# CrowBot_-V1_4-20220909.net
KiCad netlist of a schematic drawn in EAGLE
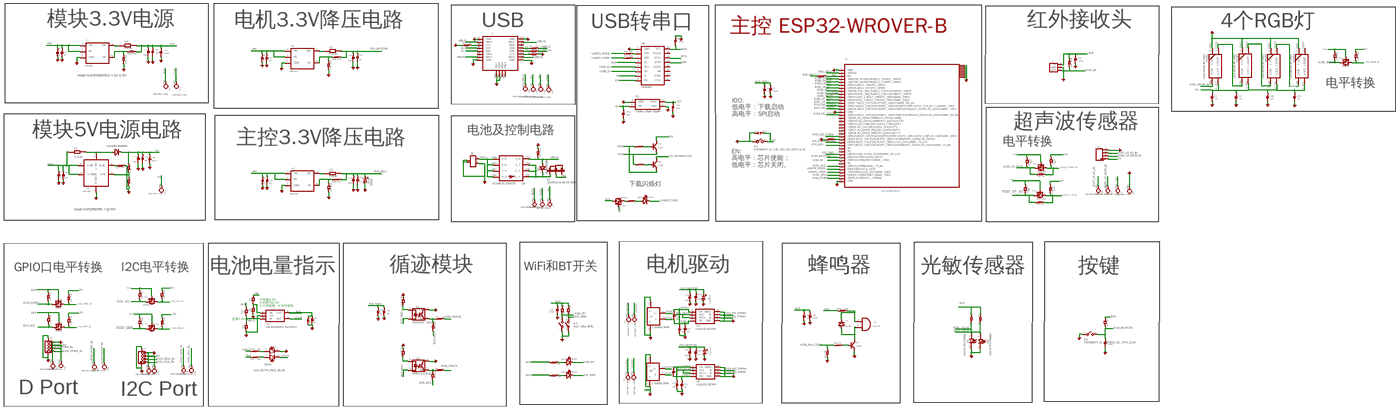
[diagram p0: schematic, sheet 1, overview]
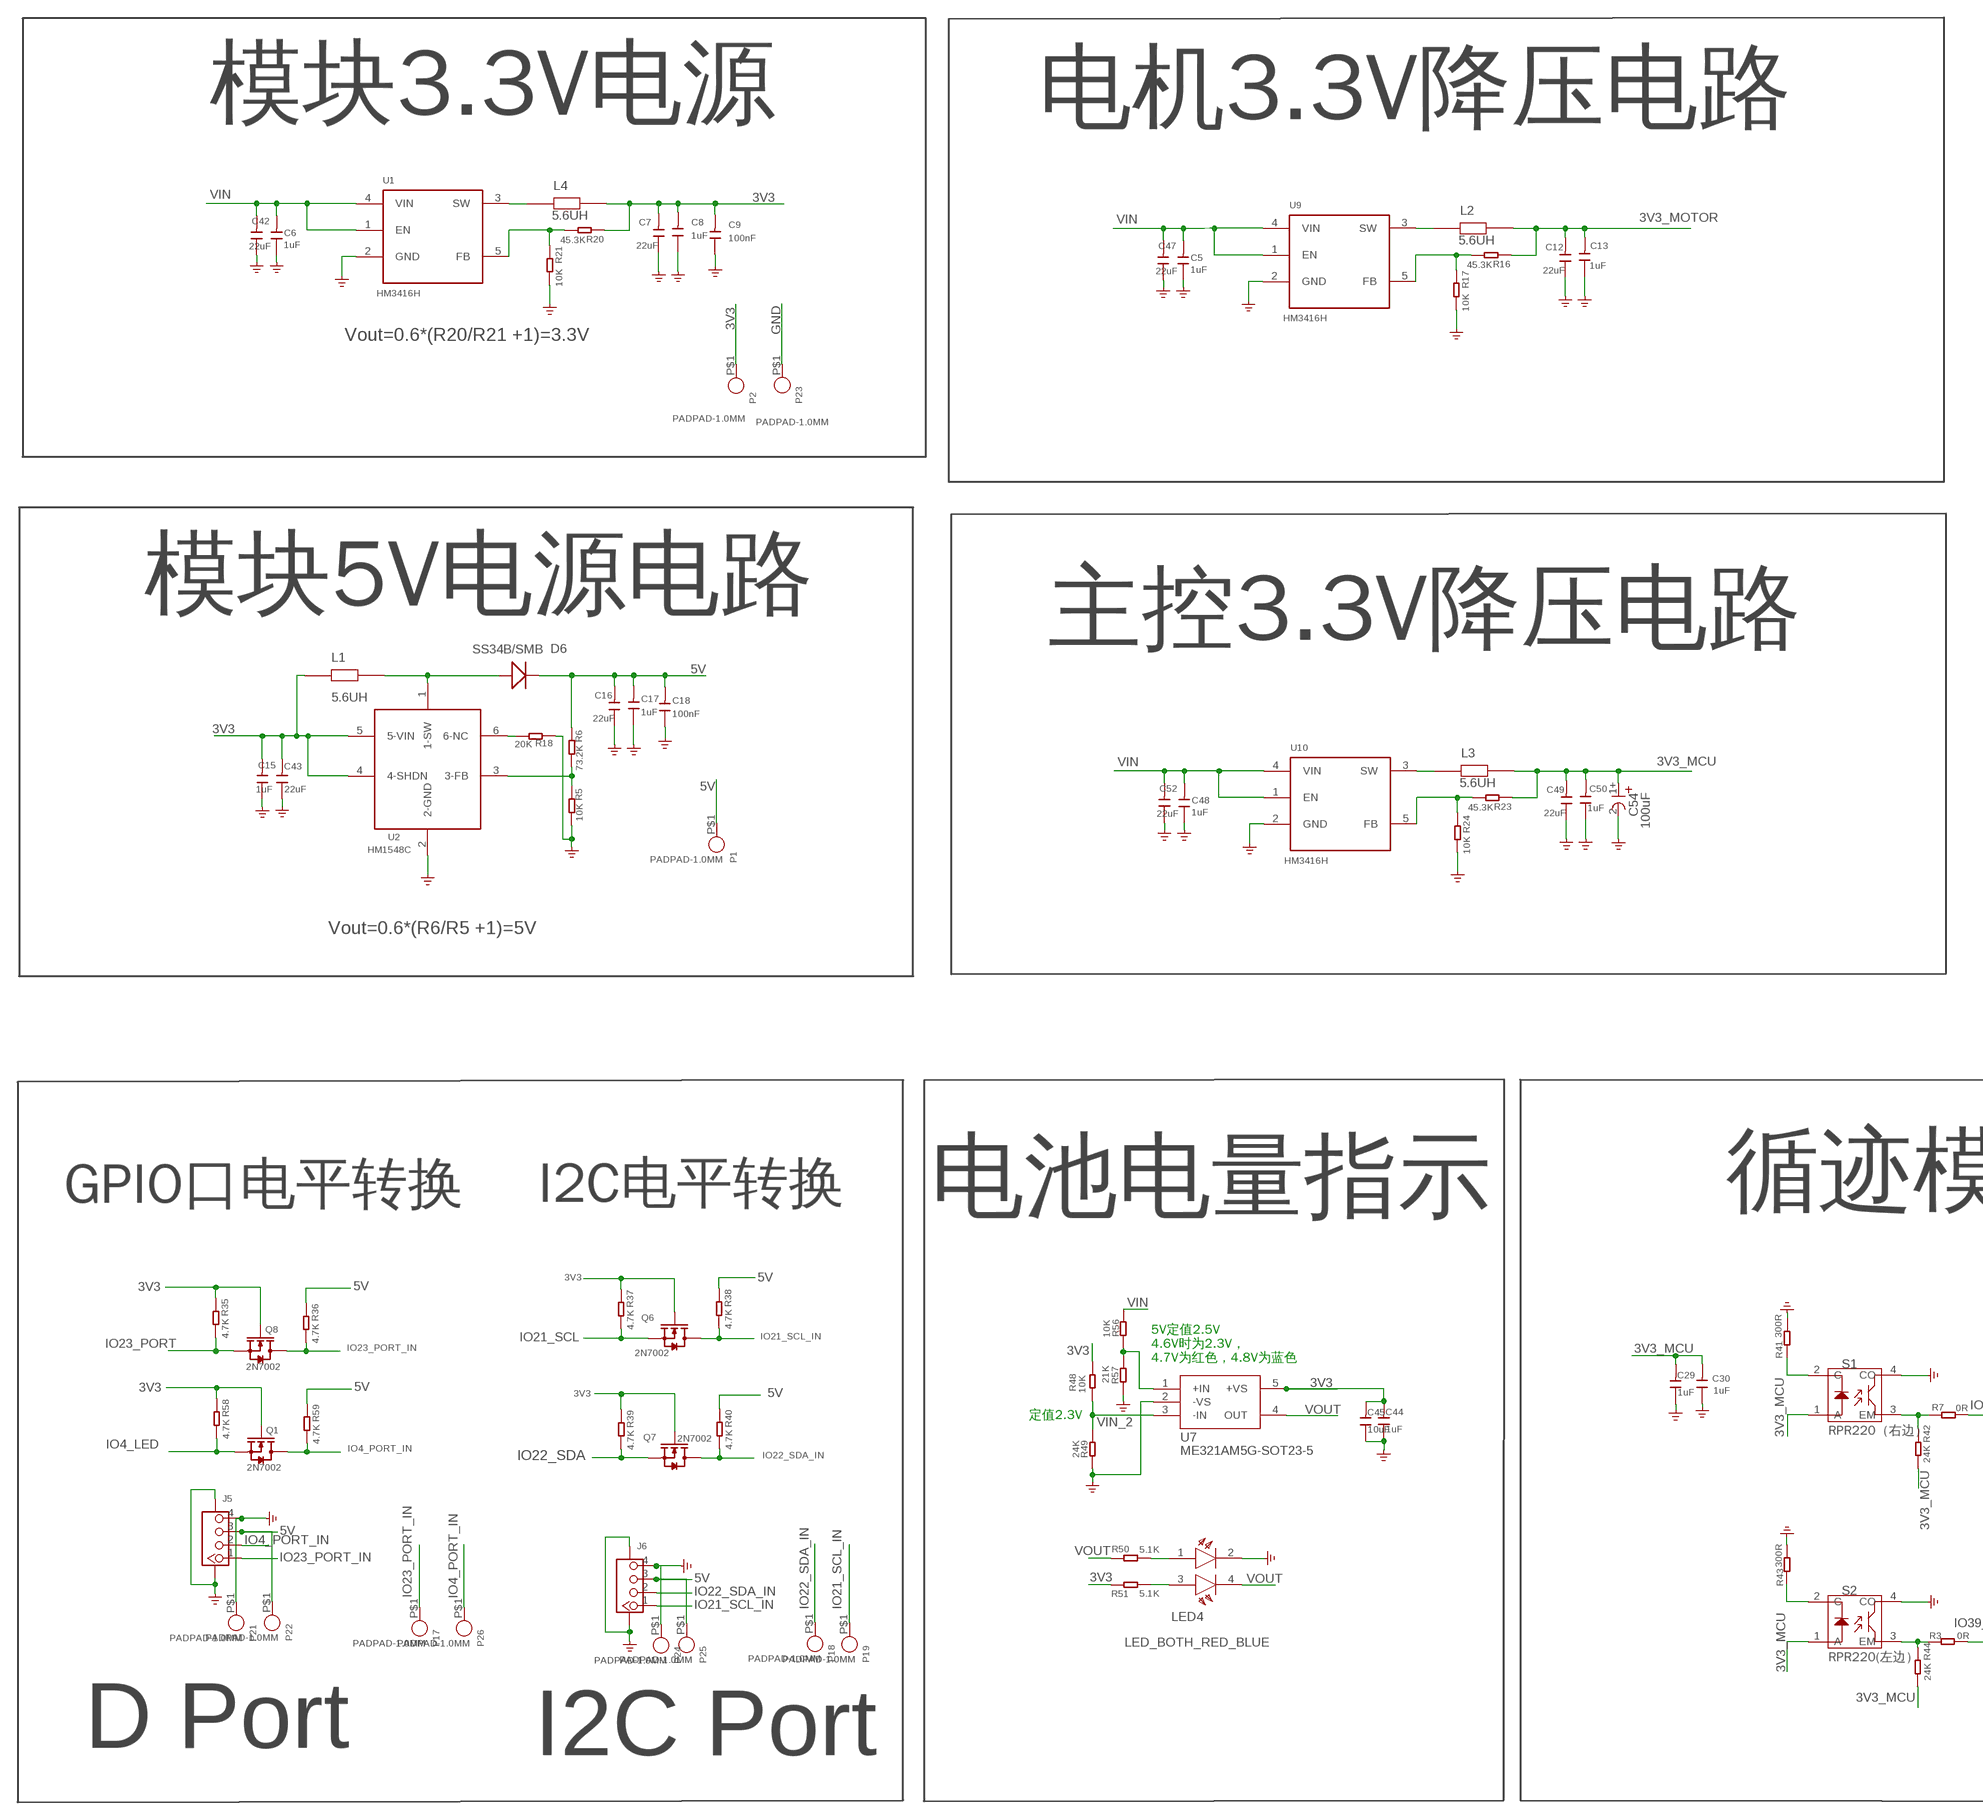
[diagram p1: schematic, sheet 1, part 1 of 4]
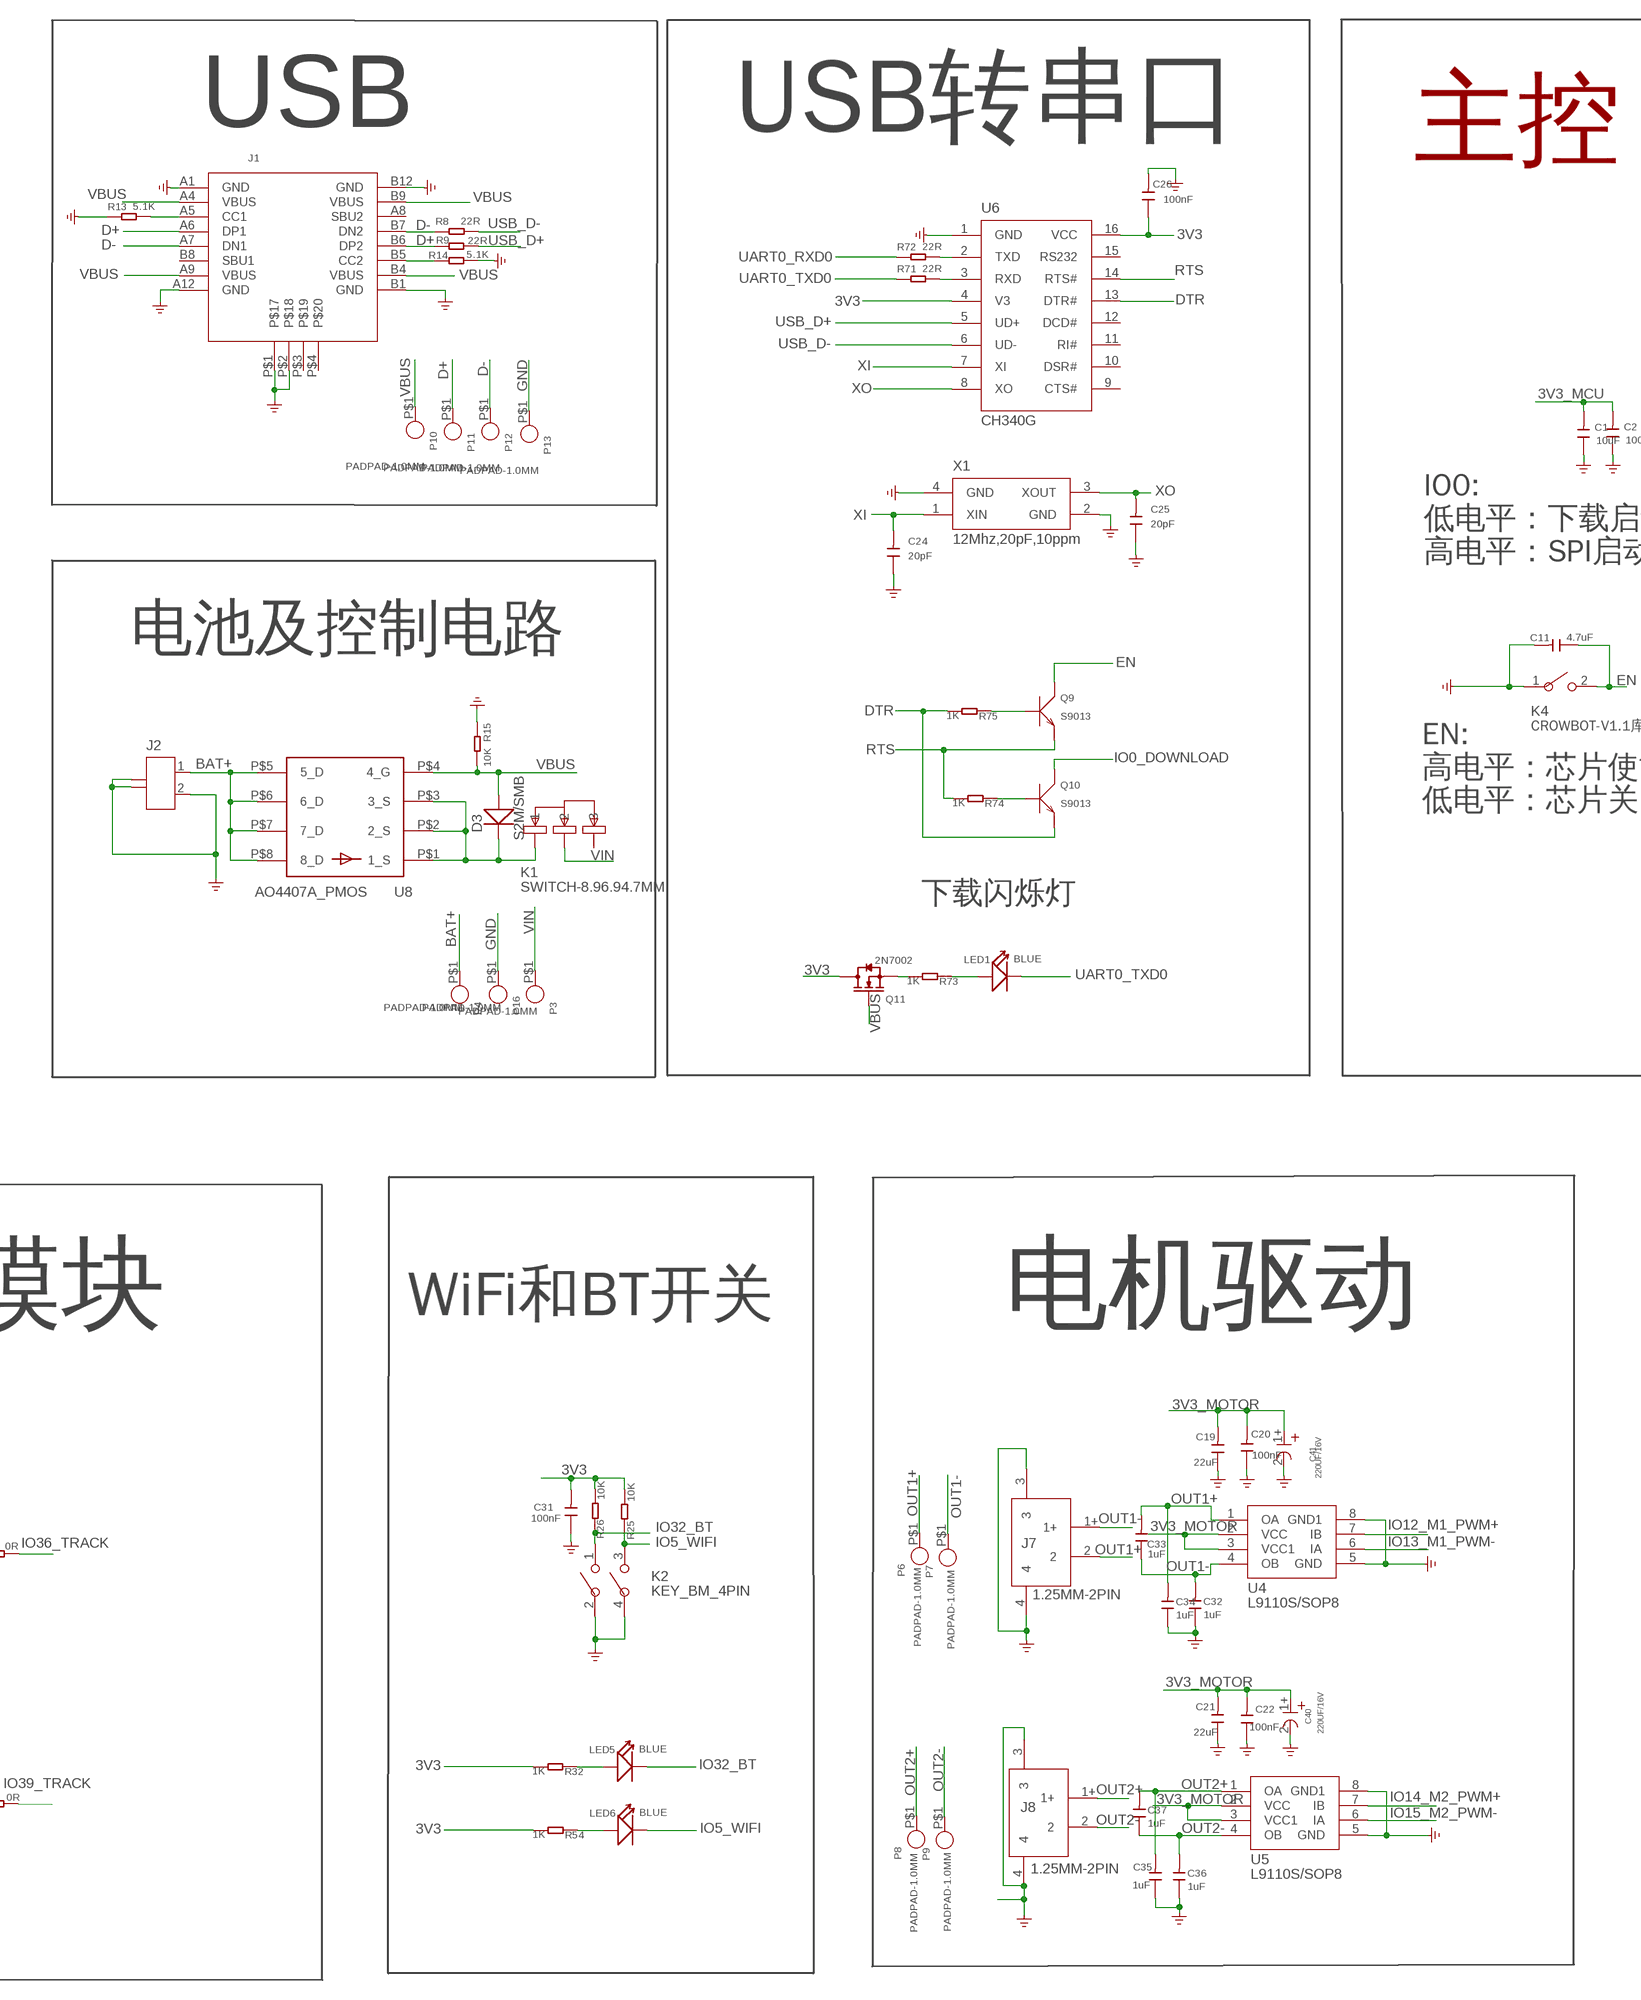
[diagram p2: schematic, sheet 1, part 2 of 4]
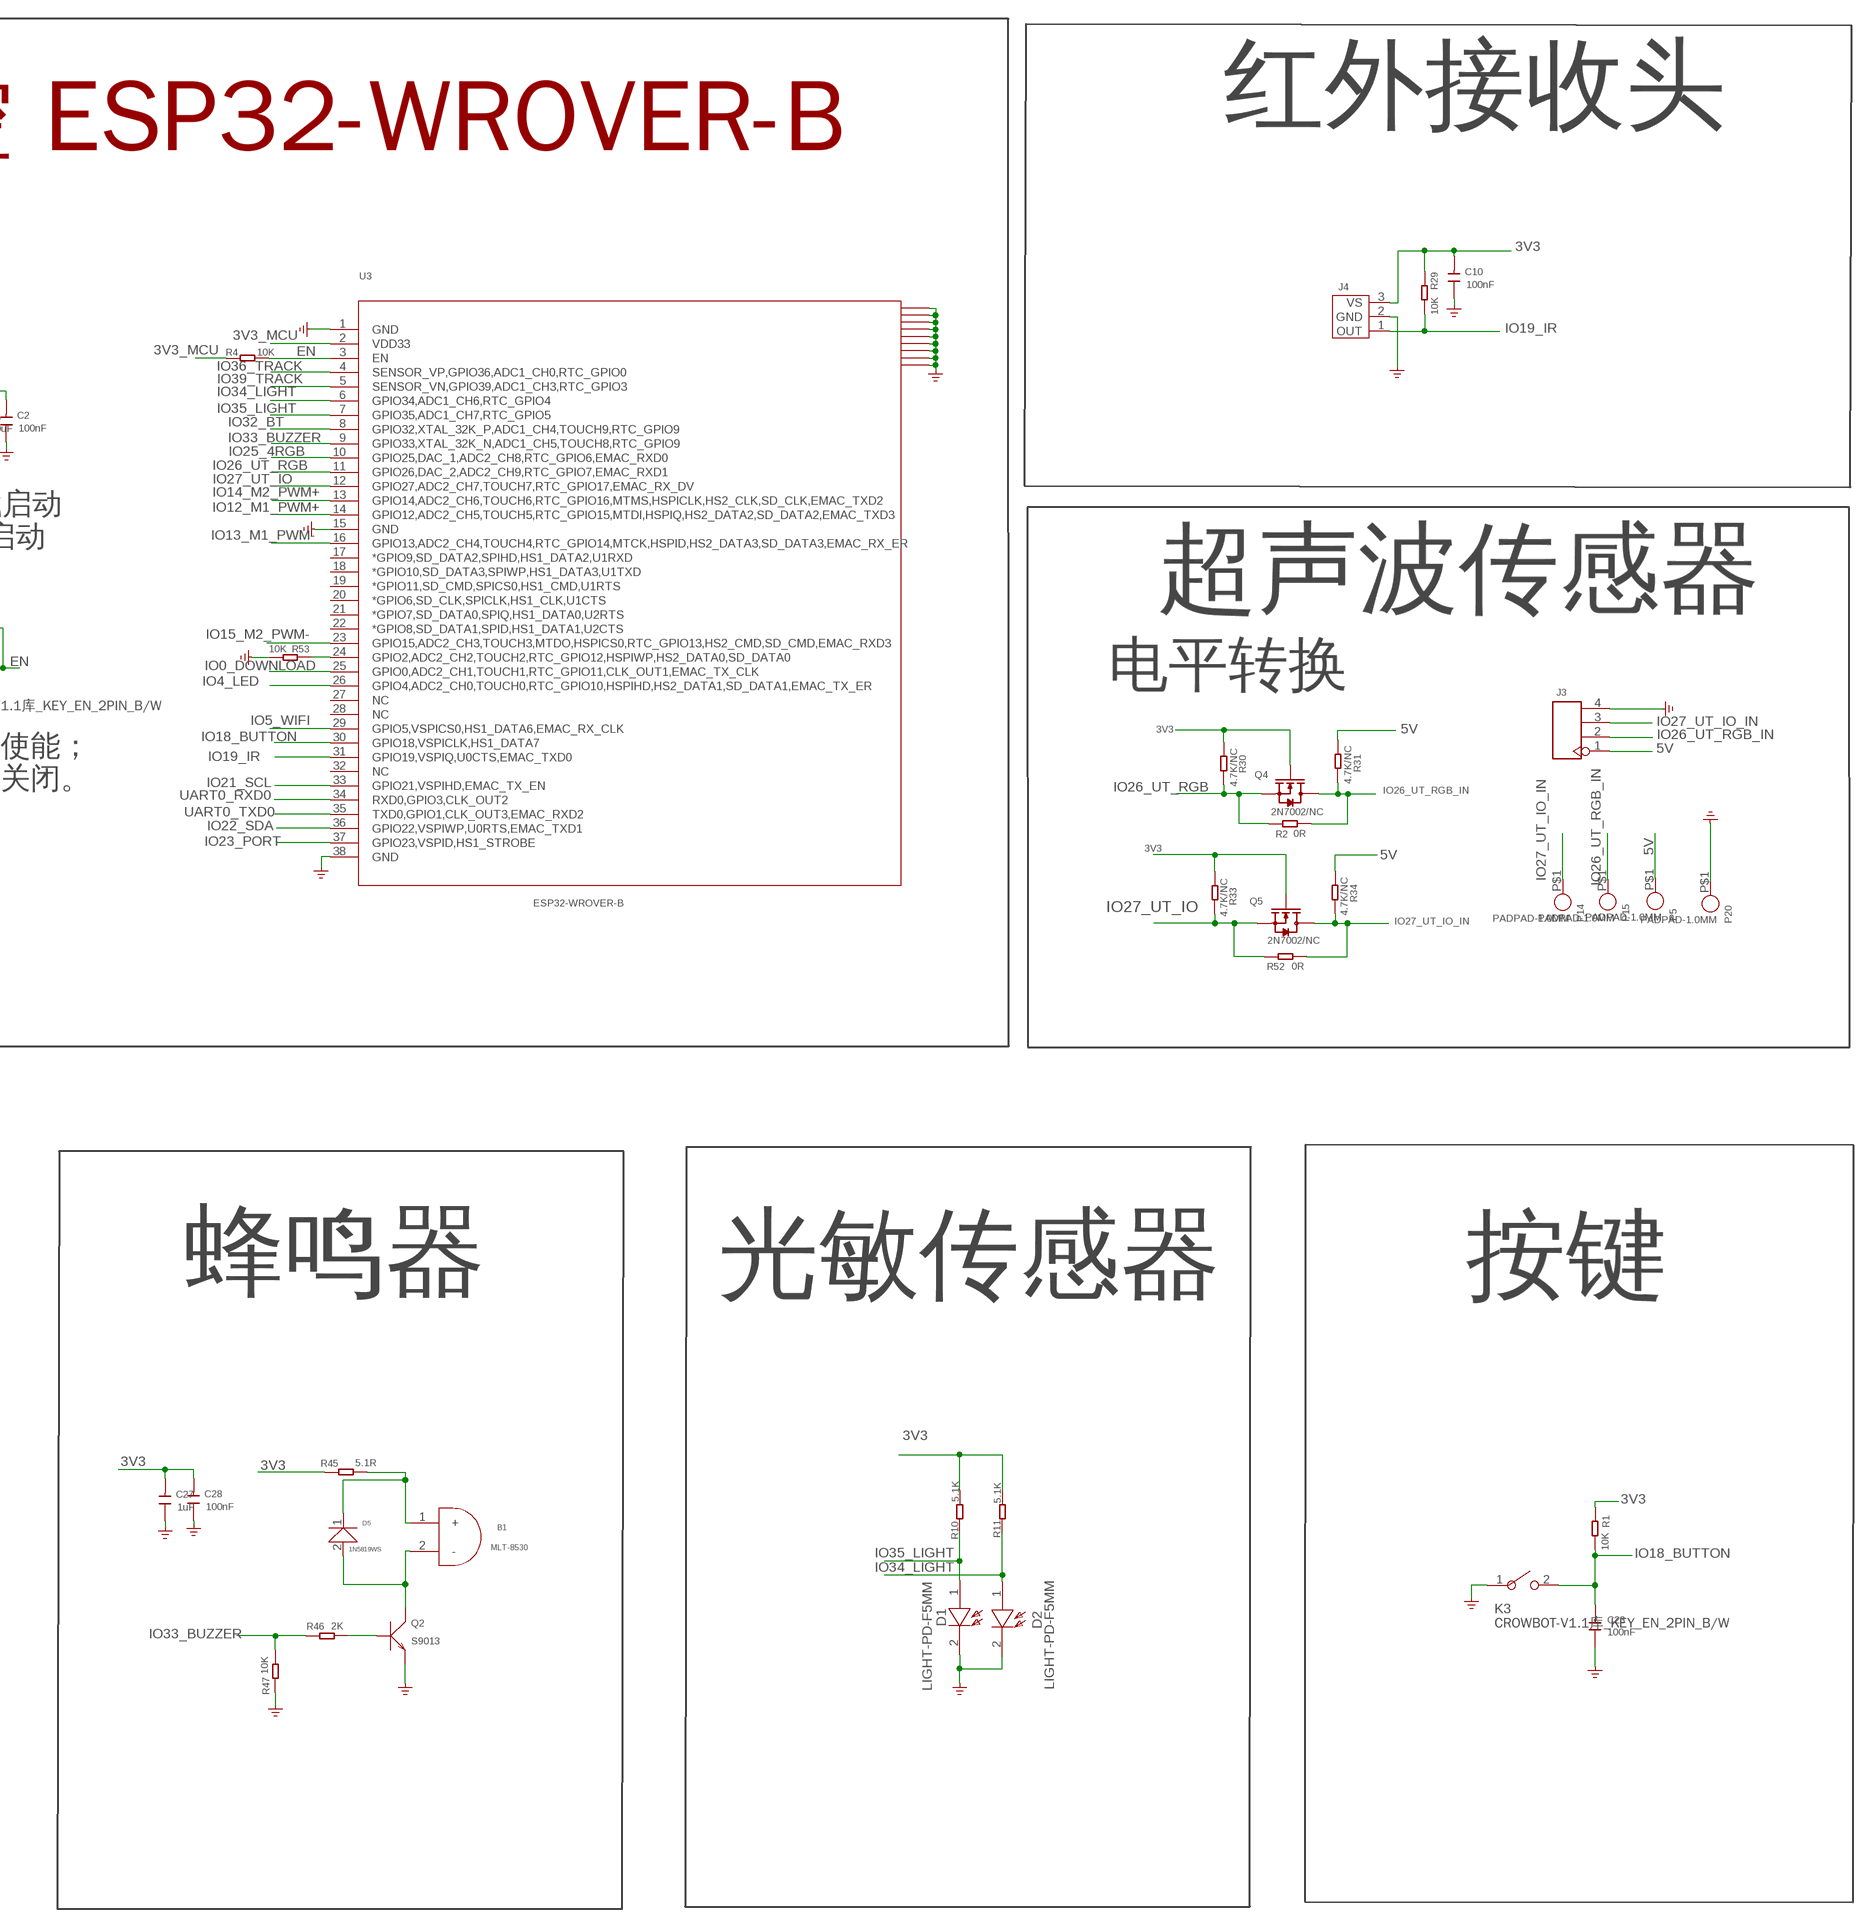
[diagram p3: schematic, sheet 1, part 3 of 4]
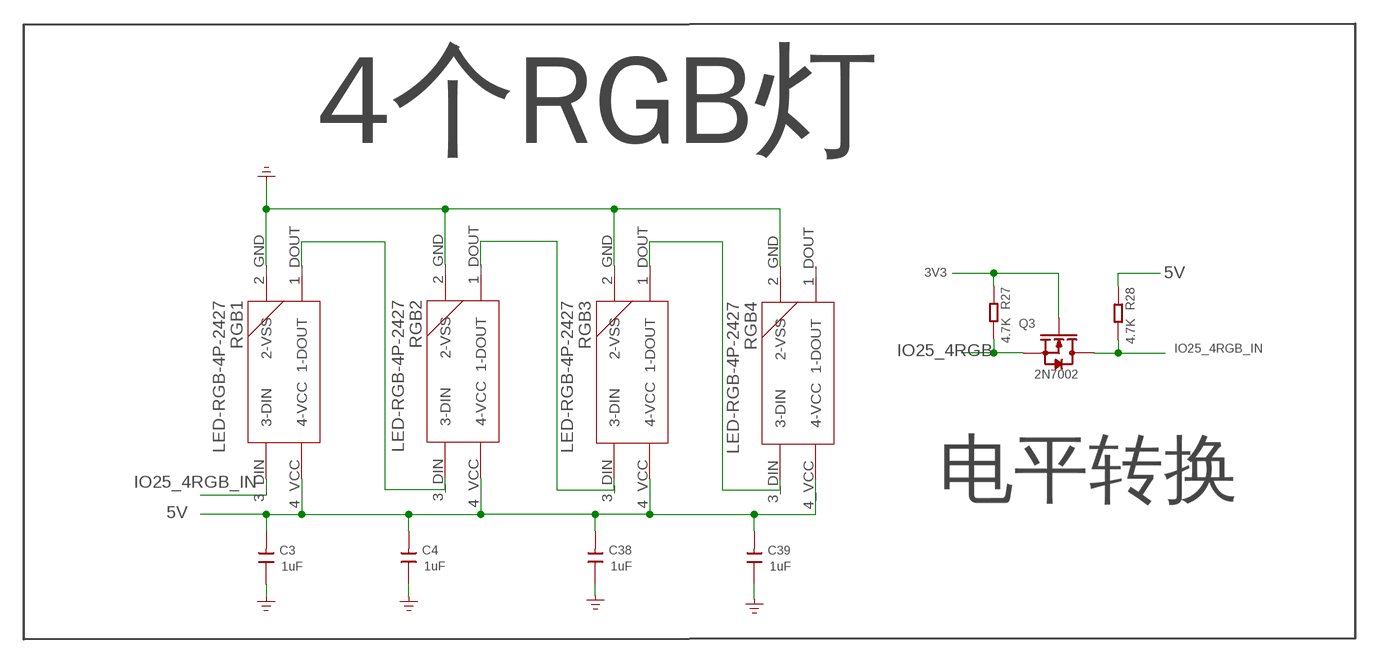
[diagram p4: schematic, sheet 1, part 4 of 4]

(export (version "E")
  (design (tool "Eeschema 10.0.6"))
  (components
    (comp (ref "B1")
      (value "MLT-8530")
      (footprint "eagle-import:MLT-8530")
      (libsource (lib "eagle-import") (part "MLT-8530"))
    )
    (comp (ref "C1")
      (value "10uF")
      (footprint "eagle-import:DISCRETE_C0603")
      (libsource (lib "eagle-import") (part "DISCRETE_C-0603"))
    )
    (comp (ref "C2")
      (value "100nF")
      (footprint "eagle-import:DISCRETE_C0603")
      (libsource (lib "eagle-import") (part "DISCRETE_C-0603"))
    )
    (comp (ref "C3")
      (value "1uF")
      (footprint "eagle-import:DISCRETE_C0603")
      (libsource (lib "eagle-import") (part "DISCRETE_C-0603"))
    )
    (comp (ref "C4")
      (value "1uF")
      (footprint "eagle-import:DISCRETE_C0603")
      (libsource (lib "eagle-import") (part "DISCRETE_C-0603"))
    )
    (comp (ref "C5")
      (value "1uF")
      (footprint "eagle-import:0603")
      (libsource (lib "eagle-import") (part "C0603"))
    )
    (comp (ref "C6")
      (value "1uF")
      (footprint "eagle-import:0603")
      (libsource (lib "eagle-import") (part "C0603"))
    )
    (comp (ref "C7")
      (value "22uF")
      (footprint "eagle-import:0805")
      (libsource (lib "eagle-import") (part "C0805"))
    )
    (comp (ref "C8")
      (value "1uF")
      (footprint "eagle-import:0603")
      (libsource (lib "eagle-import") (part "C0603"))
    )
    (comp (ref "C9")
      (value "100nF")
      (footprint "eagle-import:0603")
      (libsource (lib "eagle-import") (part "C0603"))
    )
    (comp (ref "C10")
      (value "100nF")
      (footprint "eagle-import:DISCRETE_C0603")
      (libsource (lib "eagle-import") (part "DISCRETE_C-0603"))
    )
    (comp (ref "C11")
      (value "4.7uF")
      (footprint "eagle-import:0603")
      (libsource (lib "eagle-import") (part "C0603"))
    )
    (comp (ref "C12")
      (value "22uF")
      (footprint "eagle-import:0805")
      (libsource (lib "eagle-import") (part "C0805"))
    )
    (comp (ref "C13")
      (value "1uF")
      (footprint "eagle-import:0603")
      (libsource (lib "eagle-import") (part "C0603"))
    )
    (comp (ref "C15")
      (value "1uF")
      (footprint "eagle-import:0603")
      (libsource (lib "eagle-import") (part "C0603"))
    )
    (comp (ref "C16")
      (value "22uF")
      (footprint "eagle-import:0805")
      (libsource (lib "eagle-import") (part "C0805"))
    )
    (comp (ref "C17")
      (value "1uF")
      (footprint "eagle-import:0603")
      (libsource (lib "eagle-import") (part "C0603"))
    )
    (comp (ref "C18")
      (value "100nF")
      (footprint "eagle-import:0603")
      (libsource (lib "eagle-import") (part "C0603"))
    )
    (comp (ref "C19")
      (value "22uF")
      (footprint "eagle-import:0805")
      (libsource (lib "eagle-import") (part "C0805"))
    )
    (comp (ref "C20")
      (value "100nF")
      (footprint "eagle-import:DISCRETE_C0603")
      (libsource (lib "eagle-import") (part "DISCRETE_C-0603"))
    )
    (comp (ref "C21")
      (value "22uF")
      (footprint "eagle-import:0805")
      (libsource (lib "eagle-import") (part "C0805"))
    )
    (comp (ref "C22")
      (value "100nF")
      (footprint "eagle-import:DISCRETE_C0603")
      (libsource (lib "eagle-import") (part "DISCRETE_C-0603"))
    )
    (comp (ref "C23")
      (value "100nF")
      (footprint "eagle-import:DISCRETE_C0603")
      (libsource (lib "eagle-import") (part "DISCRETE_C-0603"))
    )
    (comp (ref "C24")
      (value "20pF")
      (footprint "eagle-import:0603")
      (libsource (lib "eagle-import") (part "C0603"))
    )
    (comp (ref "C25")
      (value "20pF")
      (footprint "eagle-import:0603")
      (libsource (lib "eagle-import") (part "C0603"))
    )
    (comp (ref "C26")
      (value "100nF")
      (footprint "eagle-import:0603")
      (libsource (lib "eagle-import") (part "C0603"))
    )
    (comp (ref "C27")
      (value "1uF")
      (footprint "eagle-import:DISCRETE_C0603")
      (libsource (lib "eagle-import") (part "DISCRETE_C-0603"))
    )
    (comp (ref "C28")
      (value "100nF")
      (footprint "eagle-import:DISCRETE_C0603")
      (libsource (lib "eagle-import") (part "DISCRETE_C-0603"))
    )
    (comp (ref "C29")
      (value "1uF")
      (footprint "eagle-import:DISCRETE_C0603")
      (libsource (lib "eagle-import") (part "DISCRETE_C-0603"))
    )
    (comp (ref "C30")
      (value "1uF")
      (footprint "eagle-import:DISCRETE_C0603")
      (libsource (lib "eagle-import") (part "DISCRETE_C-0603"))
    )
    (comp (ref "C31")
      (value "100nF")
      (footprint "eagle-import:DISCRETE_C0603")
      (libsource (lib "eagle-import") (part "DISCRETE_C-0603"))
    )
    (comp (ref "C32")
      (value "1uF")
      (footprint "eagle-import:0603")
      (libsource (lib "eagle-import") (part "C0603"))
    )
    (comp (ref "C33")
      (value "1uF")
      (footprint "eagle-import:0603")
      (libsource (lib "eagle-import") (part "C0603"))
    )
    (comp (ref "C34")
      (value "1uF")
      (footprint "eagle-import:0603")
      (libsource (lib "eagle-import") (part "C0603"))
    )
    (comp (ref "C35")
      (value "1uF")
      (footprint "eagle-import:0603")
      (libsource (lib "eagle-import") (part "C0603"))
    )
    (comp (ref "C36")
      (value "1uF")
      (footprint "eagle-import:0603")
      (libsource (lib "eagle-import") (part "C0603"))
    )
    (comp (ref "C37")
      (value "1uF")
      (footprint "eagle-import:0603")
      (libsource (lib "eagle-import") (part "C0603"))
    )
    (comp (ref "C38")
      (value "1uF")
      (footprint "eagle-import:DISCRETE_C0603")
      (libsource (lib "eagle-import") (part "DISCRETE_C-0603"))
    )
    (comp (ref "C39")
      (value "1uF")
      (footprint "eagle-import:DISCRETE_C0603")
      (libsource (lib "eagle-import") (part "DISCRETE_C-0603"))
    )
    (comp (ref "C40")
      (value "220UF/16V")
      (footprint "eagle-import:CAP_220UF_SMD_6.3_5.4MM")
      (libsource (lib "eagle-import") (part "CAP_220UF_SMD_6.35.4MM"))
    )
    (comp (ref "C41")
      (value "220UF/16V")
      (footprint "eagle-import:CAP_220UF_SMD_6.3_5.4MM")
      (libsource (lib "eagle-import") (part "CAP_220UF_SMD_6.35.4MM"))
    )
    (comp (ref "C42")
      (value "22uF")
      (footprint "eagle-import:0805")
      (libsource (lib "eagle-import") (part "C0805"))
    )
    (comp (ref "C43")
      (value "22uF")
      (footprint "eagle-import:0805")
      (libsource (lib "eagle-import") (part "C0805"))
    )
    (comp (ref "C44")
      (value "1uF")
      (footprint "eagle-import:DISCRETE_C0603")
      (libsource (lib "eagle-import") (part "DISCRETE_C-0603"))
    )
    (comp (ref "C45")
      (value "10uF")
      (footprint "eagle-import:DISCRETE_C0603")
      (libsource (lib "eagle-import") (part "DISCRETE_C-0603"))
    )
    (comp (ref "C47")
      (value "22uF")
      (footprint "eagle-import:0805")
      (libsource (lib "eagle-import") (part "C0805"))
    )
    (comp (ref "C48")
      (value "1uF")
      (footprint "eagle-import:0603")
      (libsource (lib "eagle-import") (part "C0603"))
    )
    (comp (ref "C49")
      (value "22uF")
      (footprint "eagle-import:0805")
      (libsource (lib "eagle-import") (part "C0805"))
    )
    (comp (ref "C50")
      (value "1uF")
      (footprint "eagle-import:0603")
      (libsource (lib "eagle-import") (part "C0603"))
    )
    (comp (ref "C52")
      (value "22uF")
      (footprint "eagle-import:0805")
      (libsource (lib "eagle-import") (part "C0805"))
    )
    (comp (ref "C54")
      (value "100uF")
      (footprint "eagle-import:CAP-100UF-SMD-6.3_4.5MM")
      (libsource (lib "eagle-import") (part "CAP-100UF-SMD-6.34.5MM"))
    )
    (comp (ref "D1")
      (value "LIGHT-PD-F5MM")
      (footprint "eagle-import:LIGHT-PD-F5MM")
      (libsource (lib "eagle-import") (part "LIGHT-PD-F5MM"))
    )
    (comp (ref "D2")
      (value "LIGHT-PD-F5MM")
      (footprint "eagle-import:LIGHT-PD-F5MM")
      (libsource (lib "eagle-import") (part "LIGHT-PD-F5MM"))
    )
    (comp (ref "D3")
      (value "S2M/SMB")
      (footprint "eagle-import:214AB")
      (libsource (lib "eagle-import") (part "214ABDO-214AB"))
    )
    (comp (ref "D5")
      (value "1N5819WS")
      (footprint "eagle-import:SOD-323")
      (libsource (lib "eagle-import") (part "1N5819WS"))
    )
    (comp (ref "D6")
      (value "SS34B/SMB")
      (footprint "eagle-import:214AB")
      (libsource (lib "eagle-import") (part "214ABDO-214AB"))
    )
    (comp (ref "J1")
      (value "TYPEC-3.0-16P-SMD")
      (footprint "eagle-import:TYPEC-3.0-16P-SMD")
      (libsource (lib "eagle-import") (part "TYPEC-3.0-16P-SMD"))
    )
    (comp (ref "J2")
      (value "PH2.0_2P")
      (footprint "eagle-import:PH2.0_2P")
      (libsource (lib "eagle-import") (part "PH2.0_2P"))
    )
    (comp (ref "J3")
      (value "HEADER-4P-80/40MIL")
      (footprint "eagle-import:4P-2.54-80_40MIL")
      (libsource (lib "eagle-import") (part "HEADER-4P-80/40MIL"))
    )
    (comp (ref "J4")
      (value "TSOP382")
      (footprint "eagle-import:3P-2.54-4.8X5X6.95H")
      (libsource (lib "eagle-import") (part "TSOP382"))
    )
    (comp (ref "J5")
      (value "CONNECTOR_TWIG-4P-2.0-SMD-FEMALE-REINFORCE90D")
      (footprint "eagle-import:CONNECTOR_4P-SMD-2.0-90D")
      (libsource (lib "eagle-import") (part "CONNECTOR_TWIG-4P-2.0-SMD-FEMALE-REINFORCE90D"))
    )
    (comp (ref "J6")
      (value "CONNECTOR_TWIG-4P-2.0-SMD-FEMALE-REINFORCE90D")
      (footprint "eagle-import:CONNECTOR_4P-SMD-2.0-90D")
      (libsource (lib "eagle-import") (part "CONNECTOR_TWIG-4P-2.0-SMD-FEMALE-REINFORCE90D"))
    )
    (comp (ref "J7")
      (value "1.25MM-2PIN")
      (footprint "eagle-import:CROWBOT-V1.0库_1.25MM-2PIN")
      (libsource (lib "eagle-import") (part "CROWBOT-V1.0库_1.25MM-2PIN"))
    )
    (comp (ref "J8")
      (value "1.25MM-2PIN")
      (footprint "eagle-import:CROWBOT-V1.0库_1.25MM-2PIN")
      (libsource (lib "eagle-import") (part "CROWBOT-V1.0库_1.25MM-2PIN"))
    )
    (comp (ref "K1")
      (value "SWITCH-8.96.94.7MM")
      (footprint "eagle-import:SWITCH-8.9_6.9_4.7MM")
      (libsource (lib "eagle-import") (part "SWITCH-8.96.94.7MM"))
    )
    (comp (ref "K2")
      (value "KEY_BM_4PIN")
      (footprint "eagle-import:KEY_BM_4PIN")
      (libsource (lib "eagle-import") (part "KEY_BM_4PIN"))
    )
    (comp (ref "K3")
      (value "CROWBOT-V1.1库_KEY_EN_2PIN_B/W")
      (footprint "eagle-import:CROWBOT-V1.1库_KEY_EN_2PIN_B_W")
      (libsource (lib "eagle-import") (part "CROWBOT-V1.1库_KEY_EN_2PIN_B/W"))
    )
    (comp (ref "K4")
      (value "CROWBOT-V1.1库_KEY_EN_2PIN_B/W")
      (footprint "eagle-import:CROWBOT-V1.1库_KEY_EN_2PIN_B_W")
      (libsource (lib "eagle-import") (part "CROWBOT-V1.1库_KEY_EN_2PIN_B/W"))
    )
    (comp (ref "L1")
      (value "5.6UH")
      (footprint "eagle-import:CD54")
      (libsource (lib "eagle-import") (part "CROWPI2-MB-V1.4-20211012_CMP201209UD1R0MT"))
    )
    (comp (ref "L2")
      (value "5.6UH")
      (footprint "eagle-import:CD54")
      (libsource (lib "eagle-import") (part "CROWPI2-MB-V1.4-20211012_CMP201209UD1R0MT"))
    )
    (comp (ref "L3")
      (value "5.6UH")
      (footprint "eagle-import:CD54")
      (libsource (lib "eagle-import") (part "CROWPI2-MB-V1.4-20211012_CMP201209UD1R0MT"))
    )
    (comp (ref "L4")
      (value "5.6UH")
      (footprint "eagle-import:CD54")
      (libsource (lib "eagle-import") (part "CROWPI2-MB-V1.4-20211012_CMP201209UD1R0MT"))
    )
    (comp (ref "LED1")
      (value "BLUE")
      (footprint "eagle-import:DISCRETE_LED-0603")
      (libsource (lib "eagle-import") (part "DISCRETE_LED0603"))
    )
    (comp (ref "LED4")
      (value "LED_BOTH_RED_BLUE")
      (footprint "eagle-import:LED_BOTH_RED_BLUE_SMD_1.6_1.6_0.6MM")
      (libsource (lib "eagle-import") (part "LED_BOTH_RED_BLUE"))
    )
    (comp (ref "LED5")
      (value "BLUE")
      (footprint "eagle-import:DISCRETE_LED-0603")
      (libsource (lib "eagle-import") (part "DISCRETE_LED0603"))
    )
    (comp (ref "LED6")
      (value "BLUE")
      (footprint "eagle-import:DISCRETE_LED-0603")
      (libsource (lib "eagle-import") (part "DISCRETE_LED0603"))
    )
    (comp (ref "P1")
      (value "PADPAD-1.0MM")
      (footprint "eagle-import:PAD-1.0MM")
      (libsource (lib "eagle-import") (part "PADPAD-1.0MM"))
    )
    (comp (ref "P2")
      (value "PADPAD-1.0MM")
      (footprint "eagle-import:PAD-1.0MM")
      (libsource (lib "eagle-import") (part "PADPAD-1.0MM"))
    )
    (comp (ref "P3")
      (value "PADPAD-1.0MM")
      (footprint "eagle-import:PAD-1.0MM")
      (libsource (lib "eagle-import") (part "PADPAD-1.0MM"))
    )
    (comp (ref "P4")
      (value "PADPAD-1.0MM")
      (footprint "eagle-import:PAD-1.0MM")
      (libsource (lib "eagle-import") (part "PADPAD-1.0MM"))
    )
    (comp (ref "P5")
      (value "PADPAD-1.0MM")
      (footprint "eagle-import:PAD-1.0MM")
      (libsource (lib "eagle-import") (part "PADPAD-1.0MM"))
    )
    (comp (ref "P6")
      (value "PADPAD-1.0MM")
      (footprint "eagle-import:PAD-1.0MM")
      (libsource (lib "eagle-import") (part "PADPAD-1.0MM"))
    )
    (comp (ref "P7")
      (value "PADPAD-1.0MM")
      (footprint "eagle-import:PAD-1.0MM")
      (libsource (lib "eagle-import") (part "PADPAD-1.0MM"))
    )
    (comp (ref "P8")
      (value "PADPAD-1.0MM")
      (footprint "eagle-import:PAD-1.0MM")
      (libsource (lib "eagle-import") (part "PADPAD-1.0MM"))
    )
    (comp (ref "P9")
      (value "PADPAD-1.0MM")
      (footprint "eagle-import:PAD-1.0MM")
      (libsource (lib "eagle-import") (part "PADPAD-1.0MM"))
    )
    (comp (ref "P10")
      (value "PADPAD-1.0MM")
      (footprint "eagle-import:PAD-1.0MM")
      (libsource (lib "eagle-import") (part "PADPAD-1.0MM"))
    )
    (comp (ref "P11")
      (value "PADPAD-1.0MM")
      (footprint "eagle-import:PAD-1.0MM")
      (libsource (lib "eagle-import") (part "PADPAD-1.0MM"))
    )
    (comp (ref "P12")
      (value "PADPAD-1.0MM")
      (footprint "eagle-import:PAD-1.0MM")
      (libsource (lib "eagle-import") (part "PADPAD-1.0MM"))
    )
    (comp (ref "P13")
      (value "PADPAD-1.0MM")
      (footprint "eagle-import:PAD-1.0MM")
      (libsource (lib "eagle-import") (part "PADPAD-1.0MM"))
    )
    (comp (ref "P14")
      (value "PADPAD-1.0MM")
      (footprint "eagle-import:PAD-1.0MM")
      (libsource (lib "eagle-import") (part "PADPAD-1.0MM"))
    )
    (comp (ref "P15")
      (value "PADPAD-1.0MM")
      (footprint "eagle-import:PAD-1.0MM")
      (libsource (lib "eagle-import") (part "PADPAD-1.0MM"))
    )
    (comp (ref "P16")
      (value "PADPAD-1.0MM")
      (footprint "eagle-import:PAD-1.0MM")
      (libsource (lib "eagle-import") (part "PADPAD-1.0MM"))
    )
    (comp (ref "P17")
      (value "PADPAD-1.0MM")
      (footprint "eagle-import:PAD-1.0MM")
      (libsource (lib "eagle-import") (part "PADPAD-1.0MM"))
    )
    (comp (ref "P18")
      (value "PADPAD-1.0MM")
      (footprint "eagle-import:PAD-1.0MM")
      (libsource (lib "eagle-import") (part "PADPAD-1.0MM"))
    )
    (comp (ref "P19")
      (value "PADPAD-1.0MM")
      (footprint "eagle-import:PAD-1.0MM")
      (libsource (lib "eagle-import") (part "PADPAD-1.0MM"))
    )
    (comp (ref "P20")
      (value "PADPAD-1.0MM")
      (footprint "eagle-import:PAD-1.0MM")
      (libsource (lib "eagle-import") (part "PADPAD-1.0MM"))
    )
    (comp (ref "P21")
      (value "PADPAD-1.0MM")
      (footprint "eagle-import:PAD-1.0MM")
      (libsource (lib "eagle-import") (part "PADPAD-1.0MM"))
    )
    (comp (ref "P22")
      (value "PADPAD-1.0MM")
      (footprint "eagle-import:PAD-1.0MM")
      (libsource (lib "eagle-import") (part "PADPAD-1.0MM"))
    )
    (comp (ref "P23")
      (value "PADPAD-1.0MM")
      (footprint "eagle-import:PAD-1.0MM")
      (libsource (lib "eagle-import") (part "PADPAD-1.0MM"))
    )
    (comp (ref "P24")
      (value "PADPAD-1.0MM")
      (footprint "eagle-import:PAD-1.0MM")
      (libsource (lib "eagle-import") (part "PADPAD-1.0MM"))
    )
    (comp (ref "P25")
      (value "PADPAD-1.0MM")
      (footprint "eagle-import:PAD-1.0MM")
      (libsource (lib "eagle-import") (part "PADPAD-1.0MM"))
    )
    (comp (ref "P26")
      (value "PADPAD-1.0MM")
      (footprint "eagle-import:PAD-1.0MM")
      (libsource (lib "eagle-import") (part "PADPAD-1.0MM"))
    )
    (comp (ref "Q1")
      (value "2N7002")
      (footprint "eagle-import:SOT23")
      (libsource (lib "eagle-import") (part "MOSFET-N'SOT23'"))
    )
    (comp (ref "Q2")
      (value "S9013")
      (footprint "eagle-import:SOT23@1")
      (libsource (lib "eagle-import") (part "TRANSISTOR-NPN-SOT23"))
    )
    (comp (ref "Q3")
      (value "2N7002")
      (footprint "eagle-import:SOT23")
      (libsource (lib "eagle-import") (part "MOSFET-N'SOT23'"))
    )
    (comp (ref "Q4")
      (value "2N7002/NC")
      (footprint "eagle-import:SOT23")
      (libsource (lib "eagle-import") (part "MOSFET-N'SOT23'"))
    )
    (comp (ref "Q5")
      (value "2N7002/NC")
      (footprint "eagle-import:SOT23")
      (libsource (lib "eagle-import") (part "MOSFET-N'SOT23'"))
    )
    (comp (ref "Q6")
      (value "2N7002")
      (footprint "eagle-import:SOT23")
      (libsource (lib "eagle-import") (part "MOSFET-N'SOT23'"))
    )
    (comp (ref "Q7")
      (value "2N7002")
      (footprint "eagle-import:SOT23")
      (libsource (lib "eagle-import") (part "MOSFET-N'SOT23'"))
    )
    (comp (ref "Q8")
      (value "2N7002")
      (footprint "eagle-import:SOT23")
      (libsource (lib "eagle-import") (part "MOSFET-N'SOT23'"))
    )
    (comp (ref "Q9")
      (value "S9013")
      (footprint "eagle-import:SOT23@1")
      (libsource (lib "eagle-import") (part "TRANSISTOR-NPN-SOT23"))
    )
    (comp (ref "Q10")
      (value "S9013")
      (footprint "eagle-import:SOT23@1")
      (libsource (lib "eagle-import") (part "TRANSISTOR-NPN-SOT23"))
    )
    (comp (ref "Q11")
      (value "2N7002")
      (footprint "eagle-import:SOT23")
      (libsource (lib "eagle-import") (part "MOSFET-N'SOT23'"))
    )
    (comp (ref "R1")
      (value "10K")
      (footprint "eagle-import:DISCRETE_R0603")
      (libsource (lib "eagle-import") (part "DISCRETE_R-0603"))
    )
    (comp (ref "R2")
      (value "0R")
      (footprint "eagle-import:DISCRETE_R0603")
      (libsource (lib "eagle-import") (part "DISCRETE_R-0603"))
    )
    (comp (ref "R3")
      (value "0R")
      (footprint "eagle-import:0603_S")
      (libsource (lib "eagle-import") (part "005-R0603_S"))
    )
    (comp (ref "R4")
      (value "10K")
      (footprint "eagle-import:R0603")
      (libsource (lib "eagle-import") (part "R0603"))
    )
    (comp (ref "R5")
      (value "10K")
      (footprint "eagle-import:DISCRETE_R0603")
      (libsource (lib "eagle-import") (part "DISCRETE_R-0603"))
    )
    (comp (ref "R6")
      (value "73.2K")
      (footprint "eagle-import:DISCRETE_R0603")
      (libsource (lib "eagle-import") (part "DISCRETE_R-0603"))
    )
    (comp (ref "R7")
      (value "0R")
      (footprint "eagle-import:0603_S")
      (libsource (lib "eagle-import") (part "005-R0603_S"))
    )
    (comp (ref "R8")
      (value "22R")
      (footprint "eagle-import:DISCRETE_R0603")
      (libsource (lib "eagle-import") (part "DISCRETE_R-0603"))
    )
    (comp (ref "R9")
      (value "22R")
      (footprint "eagle-import:DISCRETE_R0603")
      (libsource (lib "eagle-import") (part "DISCRETE_R-0603"))
    )
    (comp (ref "R10")
      (value "5.1K")
      (footprint "eagle-import:DISCRETE_R0603")
      (libsource (lib "eagle-import") (part "DISCRETE_R-0603"))
    )
    (comp (ref "R11")
      (value "5.1K")
      (footprint "eagle-import:DISCRETE_R0603")
      (libsource (lib "eagle-import") (part "DISCRETE_R-0603"))
    )
    (comp (ref "R13")
      (value "5.1K")
      (footprint "eagle-import:DISCRETE_R0603")
      (libsource (lib "eagle-import") (part "DISCRETE_R-0603"))
    )
    (comp (ref "R14")
      (value "5.1K")
      (footprint "eagle-import:DISCRETE_R0603")
      (libsource (lib "eagle-import") (part "DISCRETE_R-0603"))
    )
    (comp (ref "R15")
      (value "10K")
      (footprint "eagle-import:DISCRETE_R0603")
      (libsource (lib "eagle-import") (part "DISCRETE_R-0603"))
    )
    (comp (ref "R16")
      (value "45.3K")
      (footprint "eagle-import:DISCRETE_R0603")
      (libsource (lib "eagle-import") (part "DISCRETE_R-0603"))
    )
    (comp (ref "R17")
      (value "10K")
      (footprint "eagle-import:DISCRETE_R0603")
      (libsource (lib "eagle-import") (part "DISCRETE_R-0603"))
    )
    (comp (ref "R18")
      (value "20K")
      (footprint "eagle-import:DISCRETE_R0603")
      (libsource (lib "eagle-import") (part "DISCRETE_R-0603"))
    )
    (comp (ref "R20")
      (value "45.3K")
      (footprint "eagle-import:DISCRETE_R0603")
      (libsource (lib "eagle-import") (part "DISCRETE_R-0603"))
    )
    (comp (ref "R21")
      (value "10K")
      (footprint "eagle-import:DISCRETE_R0603")
      (libsource (lib "eagle-import") (part "DISCRETE_R-0603"))
    )
    (comp (ref "R23")
      (value "45.3K")
      (footprint "eagle-import:DISCRETE_R0603")
      (libsource (lib "eagle-import") (part "DISCRETE_R-0603"))
    )
    (comp (ref "R24")
      (value "10K")
      (footprint "eagle-import:DISCRETE_R0603")
      (libsource (lib "eagle-import") (part "DISCRETE_R-0603"))
    )
    (comp (ref "R25")
      (value "10K")
      (footprint "eagle-import:0603_S")
      (libsource (lib "eagle-import") (part "005-R0603_S"))
    )
    (comp (ref "R26")
      (value "10K")
      (footprint "eagle-import:0603_S")
      (libsource (lib "eagle-import") (part "005-R0603_S"))
    )
    (comp (ref "R27")
      (value "4.7K")
      (footprint "eagle-import:DISCRETE_R0603")
      (libsource (lib "eagle-import") (part "DISCRETE_R-0603"))
    )
    (comp (ref "R28")
      (value "4.7K")
      (footprint "eagle-import:DISCRETE_R0603")
      (libsource (lib "eagle-import") (part "DISCRETE_R-0603"))
    )
    (comp (ref "R29")
      (value "10K")
      (footprint "eagle-import:DISCRETE_R0603")
      (libsource (lib "eagle-import") (part "DISCRETE_R-0603"))
    )
    (comp (ref "R30")
      (value "4.7K/NC")
      (footprint "eagle-import:DISCRETE_R0603")
      (libsource (lib "eagle-import") (part "DISCRETE_R-0603"))
    )
    (comp (ref "R31")
      (value "4.7K/NC")
      (footprint "eagle-import:DISCRETE_R0603")
      (libsource (lib "eagle-import") (part "DISCRETE_R-0603"))
    )
    (comp (ref "R32")
      (value "1K")
      (footprint "eagle-import:DISCRETE_R0603")
      (libsource (lib "eagle-import") (part "DISCRETE_R-0603"))
    )
    (comp (ref "R33")
      (value "4.7K/NC")
      (footprint "eagle-import:DISCRETE_R0603")
      (libsource (lib "eagle-import") (part "DISCRETE_R-0603"))
    )
    (comp (ref "R34")
      (value "4.7K/NC")
      (footprint "eagle-import:DISCRETE_R0603")
      (libsource (lib "eagle-import") (part "DISCRETE_R-0603"))
    )
    (comp (ref "R35")
      (value "4.7K")
      (footprint "eagle-import:DISCRETE_R0603")
      (libsource (lib "eagle-import") (part "DISCRETE_R-0603"))
    )
    (comp (ref "R36")
      (value "4.7K")
      (footprint "eagle-import:DISCRETE_R0603")
      (libsource (lib "eagle-import") (part "DISCRETE_R-0603"))
    )
    (comp (ref "R37")
      (value "4.7K")
      (footprint "eagle-import:DISCRETE_R0603")
      (libsource (lib "eagle-import") (part "DISCRETE_R-0603"))
    )
    (comp (ref "R38")
      (value "4.7K")
      (footprint "eagle-import:DISCRETE_R0603")
      (libsource (lib "eagle-import") (part "DISCRETE_R-0603"))
    )
    (comp (ref "R39")
      (value "4.7K")
      (footprint "eagle-import:DISCRETE_R0603")
      (libsource (lib "eagle-import") (part "DISCRETE_R-0603"))
    )
    (comp (ref "R40")
      (value "4.7K")
      (footprint "eagle-import:DISCRETE_R0603")
      (libsource (lib "eagle-import") (part "DISCRETE_R-0603"))
    )
    (comp (ref "R41")
      (value "300R")
      (footprint "eagle-import:0603_S")
      (libsource (lib "eagle-import") (part "005-R0603_S"))
    )
    (comp (ref "R42")
      (value "24K")
      (footprint "eagle-import:0603_S")
      (libsource (lib "eagle-import") (part "005-R0603_S"))
    )
    (comp (ref "R43")
      (value "300R")
      (footprint "eagle-import:0603_S")
      (libsource (lib "eagle-import") (part "005-R0603_S"))
    )
    (comp (ref "R44")
      (value "24K")
      (footprint "eagle-import:0603_S")
      (libsource (lib "eagle-import") (part "005-R0603_S"))
    )
    (comp (ref "R45")
      (value "5.1R")
      (footprint "eagle-import:R0603")
      (libsource (lib "eagle-import") (part "R0603"))
    )
    (comp (ref "R46")
      (value "2K")
      (footprint "eagle-import:DISCRETE_R0603")
      (libsource (lib "eagle-import") (part "DISCRETE_R-0603"))
    )
    (comp (ref "R47")
      (value "10K")
      (footprint "eagle-import:DISCRETE_R0603")
      (libsource (lib "eagle-import") (part "DISCRETE_R-0603"))
    )
    (comp (ref "R48")
      (value "10K")
      (footprint "eagle-import:R0603")
      (libsource (lib "eagle-import") (part "cooper_R0603"))
    )
    (comp (ref "R49")
      (value "24K")
      (footprint "eagle-import:R0603")
      (libsource (lib "eagle-import") (part "cooper_R0603"))
    )
    (comp (ref "R50")
      (value "5.1K")
      (footprint "eagle-import:DISCRETE_R0603")
      (libsource (lib "eagle-import") (part "DISCRETE_R-0603"))
    )
    (comp (ref "R51")
      (value "5.1K")
      (footprint "eagle-import:DISCRETE_R0603")
      (libsource (lib "eagle-import") (part "DISCRETE_R-0603"))
    )
    (comp (ref "R52")
      (value "0R")
      (footprint "eagle-import:DISCRETE_R0603")
      (libsource (lib "eagle-import") (part "DISCRETE_R-0603"))
    )
    (comp (ref "R53")
      (value "10K")
      (footprint "eagle-import:DISCRETE_R0603")
      (libsource (lib "eagle-import") (part "DISCRETE_R-0603"))
    )
    (comp (ref "R54")
      (value "1K")
      (footprint "eagle-import:DISCRETE_R0603")
      (libsource (lib "eagle-import") (part "DISCRETE_R-0603"))
    )
    (comp (ref "R56")
      (value "10K")
      (footprint "eagle-import:R0603")
      (libsource (lib "eagle-import") (part "cooper_R0603"))
    )
    (comp (ref "R57")
      (value "21K")
      (footprint "eagle-import:R0603")
      (libsource (lib "eagle-import") (part "cooper_R0603"))
    )
    (comp (ref "R58")
      (value "4.7K")
      (footprint "eagle-import:DISCRETE_R0603")
      (libsource (lib "eagle-import") (part "DISCRETE_R-0603"))
    )
    (comp (ref "R59")
      (value "4.7K")
      (footprint "eagle-import:DISCRETE_R0603")
      (libsource (lib "eagle-import") (part "DISCRETE_R-0603"))
    )
    (comp (ref "R71")
      (value "22R")
      (footprint "eagle-import:DISCRETE_R0603")
      (libsource (lib "eagle-import") (part "DISCRETE_R-0603"))
    )
    (comp (ref "R72")
      (value "22R")
      (footprint "eagle-import:DISCRETE_R0603")
      (libsource (lib "eagle-import") (part "DISCRETE_R-0603"))
    )
    (comp (ref "R73")
      (value "1K")
      (footprint "eagle-import:DISCRETE_R0603")
      (libsource (lib "eagle-import") (part "DISCRETE_R-0603"))
    )
    (comp (ref "R74")
      (value "1K")
      (footprint "eagle-import:DISCRETE_R0603")
      (libsource (lib "eagle-import") (part "DISCRETE_R-0603"))
    )
    (comp (ref "R75")
      (value "1K")
      (footprint "eagle-import:DISCRETE_R0603")
      (libsource (lib "eagle-import") (part "DISCRETE_R-0603"))
    )
    (comp (ref "RGB1")
      (value "LED-RGB-4P-2427")
      (footprint "eagle-import:LED-RGB-4P-SMD-2427")
      (libsource (lib "eagle-import") (part "LED-RGB-4P-2427"))
    )
    (comp (ref "RGB2")
      (value "LED-RGB-4P-2427")
      (footprint "eagle-import:LED-RGB-4P-SMD-2427")
      (libsource (lib "eagle-import") (part "LED-RGB-4P-2427"))
    )
    (comp (ref "RGB3")
      (value "LED-RGB-4P-2427")
      (footprint "eagle-import:LED-RGB-4P-SMD-2427")
      (libsource (lib "eagle-import") (part "LED-RGB-4P-2427"))
    )
    (comp (ref "RGB4")
      (value "LED-RGB-4P-2427")
      (footprint "eagle-import:LED-RGB-4P-SMD-2427")
      (libsource (lib "eagle-import") (part "LED-RGB-4P-2427"))
    )
    (comp (ref "S1")
      (value "RPR220（右边）")
      (footprint "eagle-import:4P-6.4X4.9X6.5H")
      (libsource (lib "eagle-import") (part "REFLECTIVE-PHOTOSENSOR-RPR-220"))
    )
    (comp (ref "S2")
      (value "RPR220(左边）")
      (footprint "eagle-import:4P-6.4X4.9X6.5H")
      (libsource (lib "eagle-import") (part "REFLECTIVE-PHOTOSENSOR-RPR-220"))
    )
    (comp (ref "U1")
      (value "HM3416H")
      (footprint "eagle-import:A_XBJ_SOT23-5")
      (libsource (lib "eagle-import") (part "A_XBJ_HM3420B"))
    )
    (comp (ref "U2")
      (value "HM1548C")
      (footprint "eagle-import:A_XBJ_SOT23-6")
      (libsource (lib "eagle-import") (part "HM1548/SOT23-6"))
    )
    (comp (ref "U3")
      (value "ESP32-WROVER-B")
      (footprint "eagle-import:ESP32-WROVER-B")
      (libsource (lib "eagle-import") (part "ESP32-WROVER-B"))
    )
    (comp (ref "U4")
      (value "L9110S/SOP8")
      (footprint "eagle-import:L9110S_SOP8")
      (libsource (lib "eagle-import") (part "L9110S/SOP8"))
    )
    (comp (ref "U5")
      (value "L9110S/SOP8")
      (footprint "eagle-import:L9110S_SOP8")
      (libsource (lib "eagle-import") (part "L9110S/SOP8"))
    )
    (comp (ref "U6")
      (value "CH340G")
      (footprint "eagle-import:SOP-16")
      (libsource (lib "eagle-import") (part "CH340G"))
    )
    (comp (ref "U7")
      (value "ME321AM5G-SOT23-5")
      (footprint "eagle-import:ME321AM5G-SOT23-5")
      (libsource (lib "eagle-import") (part "ME321AM5G-SOT23-5"))
    )
    (comp (ref "U8")
      (value "AO4407A_PMOS")
      (footprint "eagle-import:SOP8")
      (libsource (lib "eagle-import") (part "T_PMOS_AO4407A_SOP8"))
    )
    (comp (ref "U9")
      (value "HM3416H")
      (footprint "eagle-import:A_XBJ_SOT23-5")
      (libsource (lib "eagle-import") (part "A_XBJ_HM3420B"))
    )
    (comp (ref "U10")
      (value "HM3416H")
      (footprint "eagle-import:A_XBJ_SOT23-5")
      (libsource (lib "eagle-import") (part "A_XBJ_HM3420B"))
    )
    (comp (ref "X1")
      (value "12Mhz,20pF,10ppm")
      (footprint "eagle-import:SMD3225")
      (libsource (lib "eagle-import") (part "XTAL"))
    )
  )
  (nets
    (net (code "1") (name "/3V3") (class "Default")
      (node (ref "C10") (pin "2") (pinfunction "2_2") (pintype "passive"))
      (node (ref "C15") (pin "2") (pinfunction "2_2") (pintype "passive"))
      (node (ref "C26") (pin "1") (pinfunction "1_1") (pintype "passive"))
      (node (ref "C27") (pin "2") (pinfunction "2_2") (pintype "passive"))
      (node (ref "C28") (pin "2") (pinfunction "2_2") (pintype "passive"))
      (node (ref "C31") (pin "2") (pinfunction "2_2") (pintype "passive"))
      (node (ref "C43") (pin "2") (pinfunction "2_2") (pintype "passive"))
      (node (ref "C44") (pin "2") (pinfunction "2_2") (pintype "passive"))
      (node (ref "C45") (pin "2") (pinfunction "2_2") (pintype "passive"))
      (node (ref "C7") (pin "2") (pinfunction "2_2") (pintype "passive"))
      (node (ref "C8") (pin "2") (pinfunction "2_2") (pintype "passive"))
      (node (ref "C9") (pin "2") (pinfunction "2_2") (pintype "passive"))
      (node (ref "J4") (pin "3") (pinfunction "VS_3") (pintype "bidirectional"))
      (node (ref "L1") (pin "1") (pinfunction "1_1") (pintype "bidirectional"))
      (node (ref "L4") (pin "2") (pinfunction "2_2") (pintype "bidirectional"))
      (node (ref "P2") (pin "P$1") (pinfunction "P$1_P$1") (pintype "bidirectional"))
      (node (ref "Q1") (pin "1") (pinfunction "G_1") (pintype "passive"))
      (node (ref "Q11") (pin "3") (pinfunction "D_3") (pintype "passive"))
      (node (ref "Q3") (pin "1") (pinfunction "G_1") (pintype "passive"))
      (node (ref "Q4") (pin "1") (pinfunction "G_1") (pintype "passive"))
      (node (ref "Q5") (pin "1") (pinfunction "G_1") (pintype "passive"))
      (node (ref "Q6") (pin "1") (pinfunction "G_1") (pintype "passive"))
      (node (ref "Q7") (pin "1") (pinfunction "G_1") (pintype "passive"))
      (node (ref "Q8") (pin "1") (pinfunction "G_1") (pintype "passive"))
      (node (ref "R1") (pin "1") (pinfunction "1_1") (pintype "passive"))
      (node (ref "R10") (pin "2") (pinfunction "2_2") (pintype "passive"))
      (node (ref "R11") (pin "2") (pinfunction "2_2") (pintype "passive"))
      (node (ref "R20") (pin "1") (pinfunction "1_1") (pintype "passive"))
      (node (ref "R25") (pin "2") (pinfunction "2_2") (pintype "passive"))
      (node (ref "R26") (pin "2") (pinfunction "2_2") (pintype "passive"))
      (node (ref "R27") (pin "1") (pinfunction "1_1") (pintype "passive"))
      (node (ref "R29") (pin "1") (pinfunction "1_1") (pintype "passive"))
      (node (ref "R30") (pin "1") (pinfunction "1_1") (pintype "passive"))
      (node (ref "R32") (pin "2") (pinfunction "2_2") (pintype "passive"))
      (node (ref "R33") (pin "1") (pinfunction "1_1") (pintype "passive"))
      (node (ref "R35") (pin "1") (pinfunction "1_1") (pintype "passive"))
      (node (ref "R37") (pin "1") (pinfunction "1_1") (pintype "passive"))
      (node (ref "R39") (pin "1") (pinfunction "1_1") (pintype "passive"))
      (node (ref "R45") (pin "1") (pinfunction "1_1") (pintype "passive"))
      (node (ref "R48") (pin "1") (pinfunction "1_1") (pintype "passive"))
      (node (ref "R51") (pin "2") (pinfunction "2_2") (pintype "passive"))
      (node (ref "R54") (pin "2") (pinfunction "2_2") (pintype "passive"))
      (node (ref "R58") (pin "1") (pinfunction "1_1") (pintype "passive"))
      (node (ref "U2") (pin "4") (pinfunction "4-SHDN_4") (pintype "bidirectional"))
      (node (ref "U2") (pin "5") (pinfunction "5-VIN_5") (pintype "bidirectional"))
      (node (ref "U6") (pin "16") (pinfunction "VCC_16") (pintype "bidirectional"))
      (node (ref "U6") (pin "4") (pinfunction "V3_4") (pintype "bidirectional"))
      (node (ref "U7") (pin "5") (pinfunction "+VS_5") (pintype "bidirectional"))
    )
    (net (code "2") (name "/3V3_MCU") (class "Default")
      (node (ref "C1") (pin "2") (pinfunction "2_2") (pintype "passive"))
      (node (ref "C2") (pin "2") (pinfunction "2_2") (pintype "passive"))
      (node (ref "C29") (pin "2") (pinfunction "2_2") (pintype "passive"))
      (node (ref "C30") (pin "2") (pinfunction "2_2") (pintype "passive"))
      (node (ref "C49") (pin "2") (pinfunction "2_2") (pintype "passive"))
      (node (ref "C50") (pin "2") (pinfunction "2_2") (pintype "passive"))
      (node (ref "C54") (pin "1+") (pinfunction "1+_1+") (pintype "bidirectional"))
      (node (ref "L3") (pin "2") (pinfunction "2_2") (pintype "bidirectional"))
      (node (ref "R23") (pin "1") (pinfunction "1_1") (pintype "passive"))
      (node (ref "R4") (pin "1") (pinfunction "1_1") (pintype "passive"))
      (node (ref "R42") (pin "1") (pinfunction "1_1") (pintype "passive"))
      (node (ref "R44") (pin "1") (pinfunction "1_1") (pintype "passive"))
      (node (ref "S1") (pin "1") (pinfunction "A_1") (pintype "bidirectional"))
      (node (ref "S2") (pin "1") (pinfunction "A_1") (pintype "bidirectional"))
      (node (ref "U3") (pin "2") (pinfunction "VDD33_2") (pintype "bidirectional"))
    )
    (net (code "3") (name "/3V3_MOTOR") (class "Default")
      (node (ref "C12") (pin "2") (pinfunction "2_2") (pintype "passive"))
      (node (ref "C13") (pin "2") (pinfunction "2_2") (pintype "passive"))
      (node (ref "C19") (pin "2") (pinfunction "2_2") (pintype "passive"))
      (node (ref "C20") (pin "2") (pinfunction "2_2") (pintype "passive"))
      (node (ref "C21") (pin "2") (pinfunction "2_2") (pintype "passive"))
      (node (ref "C22") (pin "2") (pinfunction "2_2") (pintype "passive"))
      (node (ref "C40") (pin "1+") (pinfunction "1+_1+") (pintype "bidirectional"))
      (node (ref "C41") (pin "1+") (pinfunction "1+_1+") (pintype "bidirectional"))
      (node (ref "L2") (pin "2") (pinfunction "2_2") (pintype "bidirectional"))
      (node (ref "R16") (pin "1") (pinfunction "1_1") (pintype "passive"))
      (node (ref "U4") (pin "2") (pinfunction "VCC_2") (pintype "bidirectional"))
      (node (ref "U4") (pin "3") (pinfunction "VCC1_3") (pintype "bidirectional"))
      (node (ref "U5") (pin "2") (pinfunction "VCC_2") (pintype "bidirectional"))
      (node (ref "U5") (pin "3") (pinfunction "VCC1_3") (pintype "bidirectional"))
    )
    (net (code "4") (name "/5V") (class "Default")
      (node (ref "C16") (pin "2") (pinfunction "2_2") (pintype "passive"))
      (node (ref "C17") (pin "2") (pinfunction "2_2") (pintype "passive"))
      (node (ref "C18") (pin "2") (pinfunction "2_2") (pintype "passive"))
      (node (ref "C3") (pin "2") (pinfunction "2_2") (pintype "passive"))
      (node (ref "C38") (pin "2") (pinfunction "2_2") (pintype "passive"))
      (node (ref "C39") (pin "2") (pinfunction "2_2") (pintype "passive"))
      (node (ref "C4") (pin "2") (pinfunction "2_2") (pintype "passive"))
      (node (ref "D6") (pin "2") (pinfunction "-_2") (pintype "passive"))
      (node (ref "J3") (pin "1") (pinfunction "P$1_1") (pintype "bidirectional"))
      (node (ref "J5") (pin "3") (pinfunction "3_3") (pintype "bidirectional"))
      (node (ref "J6") (pin "3") (pinfunction "3_3") (pintype "bidirectional"))
      (node (ref "P1") (pin "P$1") (pinfunction "P$1_P$1") (pintype "bidirectional"))
      (node (ref "P22") (pin "P$1") (pinfunction "P$1_P$1") (pintype "bidirectional"))
      (node (ref "P25") (pin "P$1") (pinfunction "P$1_P$1") (pintype "bidirectional"))
      (node (ref "P5") (pin "P$1") (pinfunction "P$1_P$1") (pintype "bidirectional"))
      (node (ref "R28") (pin "1") (pinfunction "1_1") (pintype "passive"))
      (node (ref "R31") (pin "1") (pinfunction "1_1") (pintype "passive"))
      (node (ref "R34") (pin "1") (pinfunction "1_1") (pintype "passive"))
      (node (ref "R36") (pin "1") (pinfunction "1_1") (pintype "passive"))
      (node (ref "R38") (pin "1") (pinfunction "1_1") (pintype "passive"))
      (node (ref "R40") (pin "1") (pinfunction "1_1") (pintype "passive"))
      (node (ref "R59") (pin "1") (pinfunction "1_1") (pintype "passive"))
      (node (ref "R6") (pin "1") (pinfunction "1_1") (pintype "passive"))
      (node (ref "RGB1") (pin "4_VCC") (pinfunction "4-VCC_4_VCC") (pintype "bidirectional"))
      (node (ref "RGB2") (pin "4_VCC") (pinfunction "4-VCC_4_VCC") (pintype "bidirectional"))
      (node (ref "RGB3") (pin "4_VCC") (pinfunction "4-VCC_4_VCC") (pintype "bidirectional"))
      (node (ref "RGB4") (pin "4_VCC") (pinfunction "4-VCC_4_VCC") (pintype "bidirectional"))
    )
    (net (code "5") (name "/BAT+") (class "Default")
      (node (ref "J2") (pin "1") (pinfunction "1_1") (pintype "bidirectional"))
      (node (ref "P4") (pin "P$1") (pinfunction "P$1_P$1") (pintype "bidirectional"))
      (node (ref "U8") (pin "P$5") (pinfunction "5_D_P$5") (pintype "bidirectional"))
      (node (ref "U8") (pin "P$6") (pinfunction "6_D_P$6") (pintype "bidirectional"))
      (node (ref "U8") (pin "P$7") (pinfunction "7_D_P$7") (pintype "bidirectional"))
      (node (ref "U8") (pin "P$8") (pinfunction "8_D_P$8") (pintype "bidirectional"))
    )
    (net (code "6") (name "/D+") (class "Default")
      (node (ref "J1") (pin "A6") (pinfunction "DP1_A6") (pintype "bidirectional"))
      (node (ref "J1") (pin "B6") (pinfunction "DP2_B6") (pintype "bidirectional"))
      (node (ref "P11") (pin "P$1") (pinfunction "P$1_P$1") (pintype "bidirectional"))
      (node (ref "R9") (pin "1") (pinfunction "1_1") (pintype "passive"))
    )
    (net (code "7") (name "/D-") (class "Default")
      (node (ref "J1") (pin "A7") (pinfunction "DN1_A7") (pintype "bidirectional"))
      (node (ref "J1") (pin "B7") (pinfunction "DN2_B7") (pintype "bidirectional"))
      (node (ref "P12") (pin "P$1") (pinfunction "P$1_P$1") (pintype "bidirectional"))
      (node (ref "R8") (pin "1") (pinfunction "1_1") (pintype "passive"))
    )
    (net (code "8") (name "/DTR") (class "Default")
      (node (ref "Q10") (pin "2") (pinfunction "E_2") (pintype "passive"))
      (node (ref "R75") (pin "2") (pinfunction "2_2") (pintype "passive"))
      (node (ref "U6") (pin "13") (pinfunction "DTR#_13") (pintype "bidirectional"))
    )
    (net (code "9") (name "/EN") (class "Default")
      (node (ref "C11") (pin "1") (pinfunction "1_1") (pintype "passive"))
      (node (ref "K4") (pin "2") (pinfunction "P$2_2") (pintype "bidirectional"))
      (node (ref "Q9") (pin "3") (pinfunction "C_3") (pintype "passive"))
      (node (ref "R4") (pin "2") (pinfunction "2_2") (pintype "passive"))
      (node (ref "U3") (pin "3") (pinfunction "EN_3") (pintype "bidirectional"))
    )
    (net (code "10") (name "/IO0_DOWNLOAD") (class "Default")
      (node (ref "Q10") (pin "3") (pinfunction "C_3") (pintype "passive"))
      (node (ref "U3") (pin "25") (pinfunction "GPIO0,ADC2_CH1,TOUCH1,RTC_GPIO11,CLK_OUT1,EMAC_TX_CLK_25") (pintype "bidirectional"))
    )
    (net (code "11") (name "/IO4_LED") (class "Default")
      (node (ref "Q1") (pin "2") (pinfunction "S_2") (pintype "passive"))
      (node (ref "R58") (pin "2") (pinfunction "2_2") (pintype "passive"))
      (node (ref "U3") (pin "26") (pinfunction "GPIO4,ADC2_CH0,TOUCH0,RTC_GPIO10,HSPIHD,HS2_DATA1,SD_DATA1,EMAC_TX_ER_26") (pintype "bidirectional"))
    )
    (net (code "12") (name "/IO4_PORT_IN") (class "Default")
      (node (ref "J5") (pin "2") (pinfunction "2_2") (pintype "bidirectional"))
      (node (ref "P26") (pin "P$1") (pinfunction "P$1_P$1") (pintype "bidirectional"))
      (node (ref "Q1") (pin "3") (pinfunction "D_3") (pintype "passive"))
      (node (ref "R59") (pin "2") (pinfunction "2_2") (pintype "passive"))
    )
    (net (code "13") (name "/IO5_WIFI") (class "Default")
      (node (ref "K2") (pin "3") (pinfunction "3_3") (pintype "bidirectional"))
      (node (ref "LED6") (pin "-") (pinfunction "-_-") (pintype "passive"))
      (node (ref "R25") (pin "1") (pinfunction "1_1") (pintype "passive"))
      (node (ref "U3") (pin "29") (pinfunction "GPIO5,VSPICS0,HS1_DATA6,EMAC_RX_CLK_29") (pintype "bidirectional"))
    )
    (net (code "14") (name "/IO12_M1_PWM+") (class "Default")
      (node (ref "U3") (pin "14") (pinfunction "GPIO12,ADC2_CH5,TOUCH5,RTC_GPIO15,MTDI,HSPIQ,HS2_DATA2,SD_DATA2,EMAC_TXD3_14") (pintype "bidirectional"))
      (node (ref "U4") (pin "7") (pinfunction "IB_7") (pintype "bidirectional"))
    )
    (net (code "15") (name "/IO13_M1_PWM-") (class "Default")
      (node (ref "U3") (pin "16") (pinfunction "GPIO13,ADC2_CH4,TOUCH4,RTC_GPIO14,MTCK,HSPID,HS2_DATA3,SD_DATA3,EMAC_RX_ER_16") (pintype "bidirectional"))
      (node (ref "U4") (pin "6") (pinfunction "IA_6") (pintype "bidirectional"))
    )
    (net (code "16") (name "/IO14_M2_PWM+") (class "Default")
      (node (ref "U3") (pin "13") (pinfunction "GPIO14,ADC2_CH6,TOUCH6,RTC_GPIO16,MTMS,HSPICLK,HS2_CLK,SD_CLK,EMAC_TXD2_13") (pintype "bidirectional"))
      (node (ref "U5") (pin "7") (pinfunction "IB_7") (pintype "bidirectional"))
    )
    (net (code "17") (name "/IO15_M2_PWM-") (class "Default")
      (node (ref "U3") (pin "23") (pinfunction "GPIO15,ADC2_CH3,TOUCH3,MTDO,HSPICS0,RTC_GPIO13,HS2_CMD,SD_CMD,EMAC_RXD3_23") (pintype "bidirectional"))
      (node (ref "U5") (pin "6") (pinfunction "IA_6") (pintype "bidirectional"))
    )
    (net (code "18") (name "/IO18_BUTTON") (class "Default")
      (node (ref "C23") (pin "2") (pinfunction "2_2") (pintype "passive"))
      (node (ref "K3") (pin "2") (pinfunction "P$2_2") (pintype "bidirectional"))
      (node (ref "R1") (pin "2") (pinfunction "2_2") (pintype "passive"))
      (node (ref "U3") (pin "30") (pinfunction "GPIO18,VSPICLK,HS1_DATA7_30") (pintype "bidirectional"))
    )
    (net (code "19") (name "/IO19_IR") (class "Default")
      (node (ref "J4") (pin "1") (pinfunction "OUT_1") (pintype "bidirectional"))
      (node (ref "R29") (pin "2") (pinfunction "2_2") (pintype "passive"))
      (node (ref "U3") (pin "31") (pinfunction "GPIO19,VSPIQ,U0CTS,EMAC_TXD0_31") (pintype "bidirectional"))
    )
    (net (code "20") (name "/IO21_SCL") (class "Default")
      (node (ref "Q6") (pin "2") (pinfunction "S_2") (pintype "passive"))
      (node (ref "R37") (pin "2") (pinfunction "2_2") (pintype "passive"))
      (node (ref "U3") (pin "33") (pinfunction "GPIO21,VSPIHD,EMAC_TX_EN_33") (pintype "bidirectional"))
    )
    (net (code "21") (name "/IO21_SCL_IN") (class "Default")
      (node (ref "J6") (pin "1") (pinfunction "1_1") (pintype "bidirectional"))
      (node (ref "P19") (pin "P$1") (pinfunction "P$1_P$1") (pintype "bidirectional"))
      (node (ref "Q6") (pin "3") (pinfunction "D_3") (pintype "passive"))
      (node (ref "R38") (pin "2") (pinfunction "2_2") (pintype "passive"))
    )
    (net (code "22") (name "/IO22_SDA") (class "Default")
      (node (ref "Q7") (pin "2") (pinfunction "S_2") (pintype "passive"))
      (node (ref "R39") (pin "2") (pinfunction "2_2") (pintype "passive"))
      (node (ref "U3") (pin "36") (pinfunction "GPIO22,VSPIWP,U0RTS,EMAC_TXD1_36") (pintype "bidirectional"))
    )
    (net (code "23") (name "/IO22_SDA_IN") (class "Default")
      (node (ref "J6") (pin "2") (pinfunction "2_2") (pintype "bidirectional"))
      (node (ref "P18") (pin "P$1") (pinfunction "P$1_P$1") (pintype "bidirectional"))
      (node (ref "Q7") (pin "3") (pinfunction "D_3") (pintype "passive"))
      (node (ref "R40") (pin "2") (pinfunction "2_2") (pintype "passive"))
    )
    (net (code "24") (name "/IO23_PORT") (class "Default")
      (node (ref "Q8") (pin "2") (pinfunction "S_2") (pintype "passive"))
      (node (ref "R35") (pin "2") (pinfunction "2_2") (pintype "passive"))
      (node (ref "U3") (pin "37") (pinfunction "GPIO23,VSPID,HS1_STROBE_37") (pintype "bidirectional"))
    )
    (net (code "25") (name "/IO23_PORT_IN") (class "Default")
      (node (ref "J5") (pin "1") (pinfunction "1_1") (pintype "bidirectional"))
      (node (ref "P17") (pin "P$1") (pinfunction "P$1_P$1") (pintype "bidirectional"))
      (node (ref "Q8") (pin "3") (pinfunction "D_3") (pintype "passive"))
      (node (ref "R36") (pin "2") (pinfunction "2_2") (pintype "passive"))
    )
    (net (code "26") (name "/IO25_4RGB") (class "Default")
      (node (ref "Q3") (pin "2") (pinfunction "S_2") (pintype "passive"))
      (node (ref "R27") (pin "2") (pinfunction "2_2") (pintype "passive"))
      (node (ref "U3") (pin "10") (pinfunction "GPIO25,DAC_1,ADC2_CH8,RTC_GPIO6,EMAC_RXD0_10") (pintype "bidirectional"))
    )
    (net (code "27") (name "/IO25_4RGB_IN") (class "Default")
      (node (ref "Q3") (pin "3") (pinfunction "D_3") (pintype "passive"))
      (node (ref "R28") (pin "2") (pinfunction "2_2") (pintype "passive"))
      (node (ref "RGB1") (pin "3_DIN") (pinfunction "3-DIN_3_DIN") (pintype "bidirectional"))
    )
    (net (code "28") (name "/IO26_UT_RGB") (class "Default")
      (node (ref "Q4") (pin "2") (pinfunction "S_2") (pintype "passive"))
      (node (ref "R2") (pin "1") (pinfunction "1_1") (pintype "passive"))
      (node (ref "R30") (pin "2") (pinfunction "2_2") (pintype "passive"))
      (node (ref "U3") (pin "11") (pinfunction "GPIO26,DAC_2,ADC2_CH9,RTC_GPIO7,EMAC_RXD1_11") (pintype "bidirectional"))
    )
    (net (code "29") (name "/IO26_UT_RGB_IN") (class "Default")
      (node (ref "J3") (pin "2") (pinfunction "P$2_2") (pintype "bidirectional"))
      (node (ref "P15") (pin "P$1") (pinfunction "P$1_P$1") (pintype "bidirectional"))
      (node (ref "Q4") (pin "3") (pinfunction "D_3") (pintype "passive"))
      (node (ref "R2") (pin "2") (pinfunction "2_2") (pintype "passive"))
      (node (ref "R31") (pin "2") (pinfunction "2_2") (pintype "passive"))
    )
    (net (code "30") (name "/IO27_UT_IO") (class "Default")
      (node (ref "Q5") (pin "2") (pinfunction "S_2") (pintype "passive"))
      (node (ref "R33") (pin "2") (pinfunction "2_2") (pintype "passive"))
      (node (ref "R52") (pin "1") (pinfunction "1_1") (pintype "passive"))
      (node (ref "U3") (pin "12") (pinfunction "GPIO27,ADC2_CH7,TOUCH7,RTC_GPIO17,EMAC_RX_DV_12") (pintype "bidirectional"))
    )
    (net (code "31") (name "/IO27_UT_IO_IN") (class "Default")
      (node (ref "J3") (pin "3") (pinfunction "P$3_3") (pintype "bidirectional"))
      (node (ref "P14") (pin "P$1") (pinfunction "P$1_P$1") (pintype "bidirectional"))
      (node (ref "Q5") (pin "3") (pinfunction "D_3") (pintype "passive"))
      (node (ref "R34") (pin "2") (pinfunction "2_2") (pintype "passive"))
      (node (ref "R52") (pin "2") (pinfunction "2_2") (pintype "passive"))
    )
    (net (code "32") (name "/IO32_BT") (class "Default")
      (node (ref "K2") (pin "1") (pinfunction "1_1") (pintype "bidirectional"))
      (node (ref "LED5") (pin "-") (pinfunction "-_-") (pintype "passive"))
      (node (ref "R26") (pin "1") (pinfunction "1_1") (pintype "passive"))
      (node (ref "U3") (pin "8") (pinfunction "GPIO32,XTAL_32K_P,ADC1_CH4,TOUCH9,RTC_GPIO9_8") (pintype "bidirectional"))
    )
    (net (code "33") (name "/IO33_BUZZER") (class "Default")
      (node (ref "R46") (pin "1") (pinfunction "1_1") (pintype "passive"))
      (node (ref "R47") (pin "2") (pinfunction "2_2") (pintype "passive"))
      (node (ref "U3") (pin "9") (pinfunction "GPIO33,XTAL_32K_N,ADC1_CH5,TOUCH8,RTC_GPIO9_9") (pintype "bidirectional"))
    )
    (net (code "34") (name "/IO34_LIGHT") (class "Default")
      (node (ref "D2") (pin "1") (pinfunction "1_1") (pintype "bidirectional"))
      (node (ref "R11") (pin "1") (pinfunction "1_1") (pintype "passive"))
      (node (ref "U3") (pin "6") (pinfunction "GPIO34,ADC1_CH6,RTC_GPIO4_6") (pintype "bidirectional"))
    )
    (net (code "35") (name "/IO35_LIGHT") (class "Default")
      (node (ref "D1") (pin "1") (pinfunction "1_1") (pintype "bidirectional"))
      (node (ref "R10") (pin "1") (pinfunction "1_1") (pintype "passive"))
      (node (ref "U3") (pin "7") (pinfunction "GPIO35,ADC1_CH7,RTC_GPIO5_7") (pintype "bidirectional"))
    )
    (net (code "36") (name "/IO36_TRACK") (class "Default")
      (node (ref "R7") (pin "2") (pinfunction "2_2") (pintype "passive"))
      (node (ref "U3") (pin "4") (pinfunction "SENSOR_VP,GPIO36,ADC1_CH0,RTC_GPIO0_4") (pintype "bidirectional"))
    )
    (net (code "37") (name "/IO39_TRACK") (class "Default")
      (node (ref "R3") (pin "2") (pinfunction "2_2") (pintype "passive"))
      (node (ref "U3") (pin "5") (pinfunction "SENSOR_VN,GPIO39,ADC1_CH3,RTC_GPIO3_5") (pintype "bidirectional"))
    )
    (net (code "38") (name "/OUT1+") (class "Default")
      (node (ref "C33") (pin "2") (pinfunction "2_2") (pintype "passive"))
      (node (ref "C34") (pin "2") (pinfunction "2_2") (pintype "passive"))
      (node (ref "J7") (pin "2") (pinfunction "2_2") (pintype "power_in"))
      (node (ref "P6") (pin "P$1") (pinfunction "P$1_P$1") (pintype "bidirectional"))
      (node (ref "U4") (pin "1") (pinfunction "OA_1") (pintype "bidirectional"))
    )
    (net (code "39") (name "/OUT1-") (class "Default")
      (node (ref "C32") (pin "2") (pinfunction "2_2") (pintype "passive"))
      (node (ref "C33") (pin "1") (pinfunction "1_1") (pintype "passive"))
      (node (ref "J7") (pin "1+") (pinfunction "1+_1+") (pintype "power_in"))
      (node (ref "P7") (pin "P$1") (pinfunction "P$1_P$1") (pintype "bidirectional"))
      (node (ref "U4") (pin "4") (pinfunction "OB_4") (pintype "bidirectional"))
    )
    (net (code "40") (name "/OUT2+") (class "Default")
      (node (ref "C35") (pin "2") (pinfunction "2_2") (pintype "passive"))
      (node (ref "C37") (pin "2") (pinfunction "2_2") (pintype "passive"))
      (node (ref "J8") (pin "1+") (pinfunction "1+_1+") (pintype "power_in"))
      (node (ref "P8") (pin "P$1") (pinfunction "P$1_P$1") (pintype "bidirectional"))
      (node (ref "U5") (pin "1") (pinfunction "OA_1") (pintype "bidirectional"))
    )
    (net (code "41") (name "/OUT2-") (class "Default")
      (node (ref "C36") (pin "2") (pinfunction "2_2") (pintype "passive"))
      (node (ref "C37") (pin "1") (pinfunction "1_1") (pintype "passive"))
      (node (ref "J8") (pin "2") (pinfunction "2_2") (pintype "power_in"))
      (node (ref "P9") (pin "P$1") (pinfunction "P$1_P$1") (pintype "bidirectional"))
      (node (ref "U5") (pin "4") (pinfunction "OB_4") (pintype "bidirectional"))
    )
    (net (code "42") (name "/RTS") (class "Default")
      (node (ref "Q9") (pin "2") (pinfunction "E_2") (pintype "passive"))
      (node (ref "R74") (pin "2") (pinfunction "2_2") (pintype "passive"))
      (node (ref "U6") (pin "14") (pinfunction "RTS#_14") (pintype "bidirectional"))
    )
    (net (code "43") (name "/UART0_RXD0") (class "Default")
      (node (ref "R72") (pin "1") (pinfunction "1_1") (pintype "passive"))
      (node (ref "U3") (pin "34") (pinfunction "RXD0,GPIO3,CLK_OUT2_34") (pintype "bidirectional"))
    )
    (net (code "44") (name "/UART0_TXD0") (class "Default")
      (node (ref "LED1") (pin "-") (pinfunction "-_-") (pintype "passive"))
      (node (ref "R71") (pin "1") (pinfunction "1_1") (pintype "passive"))
      (node (ref "U3") (pin "35") (pinfunction "TXD0,GPIO1,CLK_OUT3,EMAC_RXD2_35") (pintype "bidirectional"))
    )
    (net (code "45") (name "/USB_D+") (class "Default")
      (node (ref "R9") (pin "2") (pinfunction "2_2") (pintype "passive"))
      (node (ref "U6") (pin "5") (pinfunction "UD+_5") (pintype "bidirectional"))
    )
    (net (code "46") (name "/USB_D-") (class "Default")
      (node (ref "R8") (pin "2") (pinfunction "2_2") (pintype "passive"))
      (node (ref "U6") (pin "6") (pinfunction "UD-_6") (pintype "bidirectional"))
    )
    (net (code "47") (name "/VBUS") (class "Default")
      (node (ref "D3") (pin "1") (pinfunction "+_1") (pintype "passive"))
      (node (ref "J1") (pin "A4") (pinfunction "VBUS_A4") (pintype "bidirectional"))
      (node (ref "J1") (pin "A9") (pinfunction "VBUS_A9") (pintype "bidirectional"))
      (node (ref "J1") (pin "B4") (pinfunction "VBUS_B4") (pintype "bidirectional"))
      (node (ref "J1") (pin "B9") (pinfunction "VBUS_B9") (pintype "bidirectional"))
      (node (ref "P10") (pin "P$1") (pinfunction "P$1_P$1") (pintype "bidirectional"))
      (node (ref "Q11") (pin "1") (pinfunction "G_1") (pintype "passive"))
      (node (ref "R15") (pin "2") (pinfunction "2_2") (pintype "passive"))
      (node (ref "U8") (pin "P$4") (pinfunction "4_G_P$4") (pintype "bidirectional"))
    )
    (net (code "48") (name "/VIN") (class "Default")
      (node (ref "C42") (pin "2") (pinfunction "2_2") (pintype "passive"))
      (node (ref "C47") (pin "2") (pinfunction "2_2") (pintype "passive"))
      (node (ref "C48") (pin "2") (pinfunction "2_2") (pintype "passive"))
      (node (ref "C5") (pin "2") (pinfunction "2_2") (pintype "passive"))
      (node (ref "C52") (pin "2") (pinfunction "2_2") (pintype "passive"))
      (node (ref "C6") (pin "2") (pinfunction "2_2") (pintype "passive"))
      (node (ref "K1") (pin "2") (pinfunction "2_2") (pintype "bidirectional"))
      (node (ref "P3") (pin "P$1") (pinfunction "P$1_P$1") (pintype "bidirectional"))
      (node (ref "R56") (pin "1") (pinfunction "1_1") (pintype "passive"))
      (node (ref "U1") (pin "1") (pinfunction "EN_1") (pintype "bidirectional"))
      (node (ref "U1") (pin "4") (pinfunction "VIN_4") (pintype "bidirectional"))
      (node (ref "U10") (pin "1") (pinfunction "EN_1") (pintype "bidirectional"))
      (node (ref "U10") (pin "4") (pinfunction "VIN_4") (pintype "bidirectional"))
      (node (ref "U9") (pin "1") (pinfunction "EN_1") (pintype "bidirectional"))
      (node (ref "U9") (pin "4") (pinfunction "VIN_4") (pintype "bidirectional"))
    )
    (net (code "49") (name "/VIN_2") (class "Default")
      (node (ref "R48") (pin "2") (pinfunction "2_2") (pintype "passive"))
      (node (ref "R49") (pin "1") (pinfunction "1_1") (pintype "passive"))
      (node (ref "U7") (pin "3") (pinfunction "-IN_3") (pintype "bidirectional"))
    )
    (net (code "50") (name "/VOUT") (class "Default")
      (node (ref "LED4") (pin "4") (pinfunction "4_4") (pintype "bidirectional"))
      (node (ref "R50") (pin "1") (pinfunction "1_1") (pintype "passive"))
      (node (ref "U7") (pin "4") (pinfunction "OUT_4") (pintype "bidirectional"))
    )
    (net (code "51") (name "/XI") (class "Default")
      (node (ref "C24") (pin "2") (pinfunction "2_2") (pintype "passive"))
      (node (ref "U6") (pin "7") (pinfunction "XI_7") (pintype "bidirectional"))
      (node (ref "X1") (pin "1") (pinfunction "XIN_1") (pintype "bidirectional"))
    )
    (net (code "52") (name "/XO") (class "Default")
      (node (ref "C25") (pin "2") (pinfunction "2_2") (pintype "passive"))
      (node (ref "U6") (pin "8") (pinfunction "XO_8") (pintype "bidirectional"))
      (node (ref "X1") (pin "3") (pinfunction "XOUT_3") (pintype "bidirectional"))
    )
    (net (code "53") (name "GND") (class "Default")
      (node (ref "C1") (pin "1") (pinfunction "1_1") (pintype "passive"))
      (node (ref "C10") (pin "1") (pinfunction "1_1") (pintype "passive"))
      (node (ref "C11") (pin "2") (pinfunction "2_2") (pintype "passive"))
      (node (ref "C12") (pin "1") (pinfunction "1_1") (pintype "passive"))
      (node (ref "C13") (pin "1") (pinfunction "1_1") (pintype "passive"))
      (node (ref "C15") (pin "1") (pinfunction "1_1") (pintype "passive"))
      (node (ref "C16") (pin "1") (pinfunction "1_1") (pintype "passive"))
      (node (ref "C17") (pin "1") (pinfunction "1_1") (pintype "passive"))
      (node (ref "C18") (pin "1") (pinfunction "1_1") (pintype "passive"))
      (node (ref "C19") (pin "1") (pinfunction "1_1") (pintype "passive"))
      (node (ref "C2") (pin "1") (pinfunction "1_1") (pintype "passive"))
      (node (ref "C20") (pin "1") (pinfunction "1_1") (pintype "passive"))
      (node (ref "C21") (pin "1") (pinfunction "1_1") (pintype "passive"))
      (node (ref "C22") (pin "1") (pinfunction "1_1") (pintype "passive"))
      (node (ref "C23") (pin "1") (pinfunction "1_1") (pintype "passive"))
      (node (ref "C24") (pin "1") (pinfunction "1_1") (pintype "passive"))
      (node (ref "C25") (pin "1") (pinfunction "1_1") (pintype "passive"))
      (node (ref "C26") (pin "2") (pinfunction "2_2") (pintype "passive"))
      (node (ref "C27") (pin "1") (pinfunction "1_1") (pintype "passive"))
      (node (ref "C28") (pin "1") (pinfunction "1_1") (pintype "passive"))
      (node (ref "C29") (pin "1") (pinfunction "1_1") (pintype "passive"))
      (node (ref "C3") (pin "1") (pinfunction "1_1") (pintype "passive"))
      (node (ref "C30") (pin "1") (pinfunction "1_1") (pintype "passive"))
      (node (ref "C31") (pin "1") (pinfunction "1_1") (pintype "passive"))
      (node (ref "C32") (pin "1") (pinfunction "1_1") (pintype "passive"))
      (node (ref "C34") (pin "1") (pinfunction "1_1") (pintype "passive"))
      (node (ref "C35") (pin "1") (pinfunction "1_1") (pintype "passive"))
      (node (ref "C36") (pin "1") (pinfunction "1_1") (pintype "passive"))
      (node (ref "C38") (pin "1") (pinfunction "1_1") (pintype "passive"))
      (node (ref "C39") (pin "1") (pinfunction "1_1") (pintype "passive"))
      (node (ref "C4") (pin "1") (pinfunction "1_1") (pintype "passive"))
      (node (ref "C40") (pin "2-") (pinfunction "2-_2-") (pintype "bidirectional"))
      (node (ref "C41") (pin "2-") (pinfunction "2-_2-") (pintype "bidirectional"))
      (node (ref "C42") (pin "1") (pinfunction "1_1") (pintype "passive"))
      (node (ref "C43") (pin "1") (pinfunction "1_1") (pintype "passive"))
      (node (ref "C44") (pin "1") (pinfunction "1_1") (pintype "passive"))
      (node (ref "C45") (pin "1") (pinfunction "1_1") (pintype "passive"))
      (node (ref "C47") (pin "1") (pinfunction "1_1") (pintype "passive"))
      (node (ref "C48") (pin "1") (pinfunction "1_1") (pintype "passive"))
      (node (ref "C49") (pin "1") (pinfunction "1_1") (pintype "passive"))
      (node (ref "C5") (pin "1") (pinfunction "1_1") (pintype "passive"))
      (node (ref "C50") (pin "1") (pinfunction "1_1") (pintype "passive"))
      (node (ref "C52") (pin "1") (pinfunction "1_1") (pintype "passive"))
      (node (ref "C54") (pin "2-") (pinfunction "2-_2-") (pintype "bidirectional"))
      (node (ref "C6") (pin "1") (pinfunction "1_1") (pintype "passive"))
      (node (ref "C7") (pin "1") (pinfunction "1_1") (pintype "passive"))
      (node (ref "C8") (pin "1") (pinfunction "1_1") (pintype "passive"))
      (node (ref "C9") (pin "1") (pinfunction "1_1") (pintype "passive"))
      (node (ref "D1") (pin "2") (pinfunction "2_2") (pintype "bidirectional"))
      (node (ref "D2") (pin "2") (pinfunction "2_2") (pintype "bidirectional"))
      (node (ref "J1") (pin "A1") (pinfunction "GND_A1") (pintype "bidirectional"))
      (node (ref "J1") (pin "A12") (pinfunction "GND_A12") (pintype "bidirectional"))
      (node (ref "J1") (pin "B1") (pinfunction "GND_B1") (pintype "bidirectional"))
      (node (ref "J1") (pin "B12") (pinfunction "GND_B12") (pintype "bidirectional"))
      (node (ref "J1") (pin "P$1") (pinfunction "P$17_P$1") (pintype "bidirectional"))
      (node (ref "J1") (pin "P$2") (pinfunction "P$18_P$2") (pintype "bidirectional"))
      (node (ref "J2") (pin "2") (pinfunction "2_2") (pintype "bidirectional"))
      (node (ref "J2") (pin "3") (pinfunction "3_3") (pintype "bidirectional"))
      (node (ref "J2") (pin "4") (pinfunction "4_4") (pintype "bidirectional"))
      (node (ref "J3") (pin "4") (pinfunction "P$4_4") (pintype "bidirectional"))
      (node (ref "J4") (pin "2") (pinfunction "GND_2") (pintype "bidirectional"))
      (node (ref "J5") (pin "4") (pinfunction "4_4") (pintype "bidirectional"))
      (node (ref "J5") (pin "SS1") (pinfunction "SS1_SS1") (pintype "bidirectional"))
      (node (ref "J5") (pin "SS2") (pinfunction "SS2_SS2") (pintype "bidirectional"))
      (node (ref "J6") (pin "4") (pinfunction "4_4") (pintype "bidirectional"))
      (node (ref "J6") (pin "SS1") (pinfunction "SS1_SS1") (pintype "bidirectional"))
      (node (ref "J6") (pin "SS2") (pinfunction "SS2_SS2") (pintype "bidirectional"))
      (node (ref "J7") (pin "3") (pinfunction "3_3") (pintype "power_in"))
      (node (ref "J7") (pin "4") (pinfunction "4_4") (pintype "power_in"))
      (node (ref "J8") (pin "3") (pinfunction "3_3") (pintype "power_in"))
      (node (ref "J8") (pin "4") (pinfunction "4_4") (pintype "power_in"))
      (node (ref "K2") (pin "2") (pinfunction "2_2") (pintype "bidirectional"))
      (node (ref "K2") (pin "4") (pinfunction "4_4") (pintype "bidirectional"))
      (node (ref "K3") (pin "1") (pinfunction "P$1_1") (pintype "bidirectional"))
      (node (ref "K4") (pin "1") (pinfunction "P$1_1") (pintype "bidirectional"))
      (node (ref "LED4") (pin "2") (pinfunction "2_2") (pintype "bidirectional"))
      (node (ref "P13") (pin "P$1") (pinfunction "P$1_P$1") (pintype "bidirectional"))
      (node (ref "P16") (pin "P$1") (pinfunction "P$1_P$1") (pintype "bidirectional"))
      (node (ref "P20") (pin "P$1") (pinfunction "P$1_P$1") (pintype "bidirectional"))
      (node (ref "P21") (pin "P$1") (pinfunction "P$1_P$1") (pintype "bidirectional"))
      (node (ref "P23") (pin "P$1") (pinfunction "P$1_P$1") (pintype "bidirectional"))
      (node (ref "P24") (pin "P$1") (pinfunction "P$1_P$1") (pintype "bidirectional"))
      (node (ref "Q2") (pin "2") (pinfunction "E_2") (pintype "passive"))
      (node (ref "R13") (pin "1") (pinfunction "1_1") (pintype "passive"))
      (node (ref "R14") (pin "2") (pinfunction "2_2") (pintype "passive"))
      (node (ref "R15") (pin "1") (pinfunction "1_1") (pintype "passive"))
      (node (ref "R17") (pin "2") (pinfunction "2_2") (pintype "passive"))
      (node (ref "R18") (pin "1") (pinfunction "1_1") (pintype "passive"))
      (node (ref "R21") (pin "2") (pinfunction "2_2") (pintype "passive"))
      (node (ref "R24") (pin "2") (pinfunction "2_2") (pintype "passive"))
      (node (ref "R41") (pin "1") (pinfunction "1_1") (pintype "passive"))
      (node (ref "R43") (pin "1") (pinfunction "1_1") (pintype "passive"))
      (node (ref "R47") (pin "1") (pinfunction "1_1") (pintype "passive"))
      (node (ref "R49") (pin "2") (pinfunction "2_2") (pintype "passive"))
      (node (ref "R5") (pin "2") (pinfunction "2_2") (pintype "passive"))
      (node (ref "R53") (pin "2") (pinfunction "2_2") (pintype "passive"))
      (node (ref "R57") (pin "2") (pinfunction "2_2") (pintype "passive"))
      (node (ref "RGB1") (pin "2_GND") (pinfunction "2-VSS_2_GND") (pintype "bidirectional"))
      (node (ref "RGB2") (pin "2_GND") (pinfunction "2-VSS_2_GND") (pintype "bidirectional"))
      (node (ref "RGB3") (pin "2_GND") (pinfunction "2-VSS_2_GND") (pintype "bidirectional"))
      (node (ref "RGB4") (pin "2_GND") (pinfunction "2-VSS_2_GND") (pintype "bidirectional"))
      (node (ref "S1") (pin "4") (pinfunction "CO_4") (pintype "bidirectional"))
      (node (ref "S2") (pin "4") (pinfunction "CO_4") (pintype "bidirectional"))
      (node (ref "U1") (pin "2") (pinfunction "GND_2") (pintype "bidirectional"))
      (node (ref "U10") (pin "2") (pinfunction "GND_2") (pintype "bidirectional"))
      (node (ref "U2") (pin "2") (pinfunction "2-GND_2") (pintype "bidirectional"))
      (node (ref "U3") (pin "1") (pinfunction "GND_1") (pintype "bidirectional"))
      (node (ref "U3") (pin "15") (pinfunction "GND_15") (pintype "bidirectional"))
      (node (ref "U3") (pin "38") (pinfunction "GND_38") (pintype "bidirectional"))
      (node (ref "U3") (pin "39") (pinfunction "GND_39") (pintype "bidirectional"))
      (node (ref "U3") (pin "40") (pinfunction "GND_40") (pintype "bidirectional"))
      (node (ref "U3") (pin "41") (pinfunction "GND_41") (pintype "bidirectional"))
      (node (ref "U3") (pin "42") (pinfunction "GND_42") (pintype "bidirectional"))
      (node (ref "U3") (pin "43") (pinfunction "GND_43") (pintype "bidirectional"))
      (node (ref "U3") (pin "44") (pinfunction "GND_44") (pintype "bidirectional"))
      (node (ref "U3") (pin "45") (pinfunction "GND_45") (pintype "bidirectional"))
      (node (ref "U3") (pin "46") (pinfunction "GND_46") (pintype "bidirectional"))
      (node (ref "U3") (pin "47") (pinfunction "GND_47") (pintype "bidirectional"))
      (node (ref "U4") (pin "5") (pinfunction "GND_5") (pintype "bidirectional"))
      (node (ref "U4") (pin "8") (pinfunction "GND1_8") (pintype "bidirectional"))
      (node (ref "U5") (pin "5") (pinfunction "GND_5") (pintype "bidirectional"))
      (node (ref "U5") (pin "8") (pinfunction "GND1_8") (pintype "bidirectional"))
      (node (ref "U6") (pin "1") (pinfunction "GND_1") (pintype "bidirectional"))
      (node (ref "U7") (pin "2") (pinfunction "-VS_2") (pintype "bidirectional"))
      (node (ref "U9") (pin "2") (pinfunction "GND_2") (pintype "bidirectional"))
      (node (ref "X1") (pin "2") (pinfunction "GND_2") (pintype "bidirectional"))
      (node (ref "X1") (pin "4") (pinfunction "GND_4") (pintype "bidirectional"))
    )
    (net (code "54") (name "Net-(B1-+)") (class "Default")
      (node (ref "B1") (pin "1") (pinfunction "+_1") (pintype "bidirectional"))
      (node (ref "D5") (pin "1") (pinfunction "-_1") (pintype "bidirectional"))
      (node (ref "R45") (pin "2") (pinfunction "2_2") (pintype "passive"))
    )
    (net (code "55") (name "Net-(B1--)") (class "Default")
      (node (ref "B1") (pin "2") (pinfunction "-_2") (pintype "bidirectional"))
      (node (ref "D5") (pin "2") (pinfunction "+_2") (pintype "bidirectional"))
      (node (ref "Q2") (pin "3") (pinfunction "C_3") (pintype "passive"))
    )
    (net (code "56") (name "Net-(D3--)") (class "Default")
      (node (ref "D3") (pin "2") (pinfunction "-_2") (pintype "passive"))
      (node (ref "K1") (pin "1") (pinfunction "1_1") (pintype "bidirectional"))
      (node (ref "U8") (pin "P$1") (pinfunction "1_S_P$1") (pintype "bidirectional"))
      (node (ref "U8") (pin "P$2") (pinfunction "2_S_P$2") (pintype "bidirectional"))
      (node (ref "U8") (pin "P$3") (pinfunction "3_S_P$3") (pintype "bidirectional"))
    )
    (net (code "57") (name "Net-(D6-+)") (class "Default")
      (node (ref "D6") (pin "1") (pinfunction "+_1") (pintype "passive"))
      (node (ref "L1") (pin "2") (pinfunction "2_2") (pintype "bidirectional"))
      (node (ref "U2") (pin "1") (pinfunction "1-SW_1") (pintype "bidirectional"))
    )
    (net (code "58") (name "Net-(J1-CC1)") (class "Default")
      (node (ref "J1") (pin "A5") (pinfunction "CC1_A5") (pintype "bidirectional"))
      (node (ref "R13") (pin "2") (pinfunction "2_2") (pintype "passive"))
    )
    (net (code "59") (name "Net-(J1-CC2)") (class "Default")
      (node (ref "J1") (pin "B5") (pinfunction "CC2_B5") (pintype "bidirectional"))
      (node (ref "R14") (pin "1") (pinfunction "1_1") (pintype "passive"))
    )
    (net (code "60") (name "Net-(LED1-Pad+)") (class "Default")
      (node (ref "LED1") (pin "+") (pinfunction "+_+") (pintype "passive"))
      (node (ref "R73") (pin "1") (pinfunction "1_1") (pintype "passive"))
    )
    (net (code "61") (name "Net-(LED4-Pad1)") (class "Default")
      (node (ref "LED4") (pin "1") (pinfunction "1_1") (pintype "bidirectional"))
      (node (ref "R50") (pin "2") (pinfunction "2_2") (pintype "passive"))
    )
    (net (code "62") (name "Net-(LED4-Pad3)") (class "Default")
      (node (ref "LED4") (pin "3") (pinfunction "3_3") (pintype "bidirectional"))
      (node (ref "R51") (pin "1") (pinfunction "1_1") (pintype "passive"))
    )
    (net (code "63") (name "Net-(LED5-Pad+)") (class "Default")
      (node (ref "LED5") (pin "+") (pinfunction "+_+") (pintype "passive"))
      (node (ref "R32") (pin "1") (pinfunction "1_1") (pintype "passive"))
    )
    (net (code "64") (name "Net-(LED6-Pad+)") (class "Default")
      (node (ref "LED6") (pin "+") (pinfunction "+_+") (pintype "passive"))
      (node (ref "R54") (pin "1") (pinfunction "1_1") (pintype "passive"))
    )
    (net (code "65") (name "Net-(Q2-B)") (class "Default")
      (node (ref "Q2") (pin "1") (pinfunction "B_1") (pintype "passive"))
      (node (ref "R46") (pin "2") (pinfunction "2_2") (pintype "passive"))
    )
    (net (code "66") (name "Net-(Q9-B)") (class "Default")
      (node (ref "Q9") (pin "1") (pinfunction "B_1") (pintype "passive"))
      (node (ref "R75") (pin "1") (pinfunction "1_1") (pintype "passive"))
    )
    (net (code "67") (name "Net-(Q10-B)") (class "Default")
      (node (ref "Q10") (pin "1") (pinfunction "B_1") (pintype "passive"))
      (node (ref "R74") (pin "1") (pinfunction "1_1") (pintype "passive"))
    )
    (net (code "68") (name "Net-(Q11-S)") (class "Default")
      (node (ref "Q11") (pin "2") (pinfunction "S_2") (pintype "passive"))
      (node (ref "R73") (pin "2") (pinfunction "2_2") (pintype "passive"))
    )
    (net (code "69") (name "Net-(RGB1-1-DOUT)") (class "Default")
      (node (ref "RGB1") (pin "1_DOUT") (pinfunction "1-DOUT_1_DOUT") (pintype "bidirectional"))
      (node (ref "RGB2") (pin "3_DIN") (pinfunction "3-DIN_3_DIN") (pintype "bidirectional"))
    )
    (net (code "70") (name "Net-(RGB2-1-DOUT)") (class "Default")
      (node (ref "RGB2") (pin "1_DOUT") (pinfunction "1-DOUT_1_DOUT") (pintype "bidirectional"))
      (node (ref "RGB3") (pin "3_DIN") (pinfunction "3-DIN_3_DIN") (pintype "bidirectional"))
    )
    (net (code "71") (name "Net-(RGB3-1-DOUT)") (class "Default")
      (node (ref "RGB3") (pin "1_DOUT") (pinfunction "1-DOUT_1_DOUT") (pintype "bidirectional"))
      (node (ref "RGB4") (pin "3_DIN") (pinfunction "3-DIN_3_DIN") (pintype "bidirectional"))
    )
    (net (code "72") (name "Net-(S1-C)") (class "Default")
      (node (ref "R41") (pin "2") (pinfunction "2_2") (pintype "passive"))
      (node (ref "S1") (pin "2") (pinfunction "C_2") (pintype "bidirectional"))
    )
    (net (code "73") (name "Net-(S1-EM)") (class "Default")
      (node (ref "R42") (pin "2") (pinfunction "2_2") (pintype "passive"))
      (node (ref "R7") (pin "1") (pinfunction "1_1") (pintype "passive"))
      (node (ref "S1") (pin "3") (pinfunction "EM_3") (pintype "bidirectional"))
    )
    (net (code "74") (name "Net-(S2-C)") (class "Default")
      (node (ref "R43") (pin "2") (pinfunction "2_2") (pintype "passive"))
      (node (ref "S2") (pin "2") (pinfunction "C_2") (pintype "bidirectional"))
    )
    (net (code "75") (name "Net-(S2-EM)") (class "Default")
      (node (ref "R3") (pin "1") (pinfunction "1_1") (pintype "passive"))
      (node (ref "R44") (pin "2") (pinfunction "2_2") (pintype "passive"))
      (node (ref "S2") (pin "3") (pinfunction "EM_3") (pintype "bidirectional"))
    )
    (net (code "76") (name "Net-(U1-FB)") (class "Default")
      (node (ref "R20") (pin "2") (pinfunction "2_2") (pintype "passive"))
      (node (ref "R21") (pin "1") (pinfunction "1_1") (pintype "passive"))
      (node (ref "U1") (pin "5") (pinfunction "FB_5") (pintype "bidirectional"))
    )
    (net (code "77") (name "Net-(U1-SW)") (class "Default")
      (node (ref "L4") (pin "1") (pinfunction "1_1") (pintype "bidirectional"))
      (node (ref "U1") (pin "3") (pinfunction "SW_3") (pintype "bidirectional"))
    )
    (net (code "78") (name "Net-(U2-3-FB)") (class "Default")
      (node (ref "R5") (pin "1") (pinfunction "1_1") (pintype "passive"))
      (node (ref "R6") (pin "2") (pinfunction "2_2") (pintype "passive"))
      (node (ref "U2") (pin "3") (pinfunction "3-FB_3") (pintype "bidirectional"))
    )
    (net (code "79") (name "Net-(U2-6-NC)") (class "Default")
      (node (ref "R18") (pin "2") (pinfunction "2_2") (pintype "passive"))
      (node (ref "U2") (pin "6") (pinfunction "6-NC_6") (pintype "bidirectional"))
    )
    (net (code "80") (name "Net-(U3-GPIO2,ADC2_CH2,TOUCH2,RTC_GPIO12,HSPIWP,HS2_DATA0,SD_DATA0)") (class "Default")
      (node (ref "R53") (pin "1") (pinfunction "1_1") (pintype "passive"))
      (node (ref "U3") (pin "24") (pinfunction "GPIO2,ADC2_CH2,TOUCH2,RTC_GPIO12,HSPIWP,HS2_DATA0,SD_DATA0_24") (pintype "bidirectional"))
    )
    (net (code "81") (name "Net-(U6-RXD)") (class "Default")
      (node (ref "R71") (pin "2") (pinfunction "2_2") (pintype "passive"))
      (node (ref "U6") (pin "3") (pinfunction "RXD_3") (pintype "bidirectional"))
    )
    (net (code "82") (name "Net-(U6-TXD)") (class "Default")
      (node (ref "R72") (pin "2") (pinfunction "2_2") (pintype "passive"))
      (node (ref "U6") (pin "2") (pinfunction "TXD_2") (pintype "bidirectional"))
    )
    (net (code "83") (name "Net-(U7-+IN)") (class "Default")
      (node (ref "R56") (pin "2") (pinfunction "2_2") (pintype "passive"))
      (node (ref "R57") (pin "1") (pinfunction "1_1") (pintype "passive"))
      (node (ref "U7") (pin "1") (pinfunction "+IN_1") (pintype "bidirectional"))
    )
    (net (code "84") (name "Net-(U9-FB)") (class "Default")
      (node (ref "R16") (pin "2") (pinfunction "2_2") (pintype "passive"))
      (node (ref "R17") (pin "1") (pinfunction "1_1") (pintype "passive"))
      (node (ref "U9") (pin "5") (pinfunction "FB_5") (pintype "bidirectional"))
    )
    (net (code "85") (name "Net-(U9-SW)") (class "Default")
      (node (ref "L2") (pin "1") (pinfunction "1_1") (pintype "bidirectional"))
      (node (ref "U9") (pin "3") (pinfunction "SW_3") (pintype "bidirectional"))
    )
    (net (code "86") (name "Net-(U10-FB)") (class "Default")
      (node (ref "R23") (pin "2") (pinfunction "2_2") (pintype "passive"))
      (node (ref "R24") (pin "1") (pinfunction "1_1") (pintype "passive"))
      (node (ref "U10") (pin "5") (pinfunction "FB_5") (pintype "bidirectional"))
    )
    (net (code "87") (name "Net-(U10-SW)") (class "Default")
      (node (ref "L3") (pin "1") (pinfunction "1_1") (pintype "bidirectional"))
      (node (ref "U10") (pin "3") (pinfunction "SW_3") (pintype "bidirectional"))
    )
    (net (code "88") (name "unconnected-(J1-P$19-PadP$3)") (class "Default")
      (node (ref "J1") (pin "P$3") (pinfunction "P$19_P$3") (pintype "bidirectional"))
    )
    (net (code "89") (name "unconnected-(J1-P$20-PadP$4)") (class "Default")
      (node (ref "J1") (pin "P$4") (pinfunction "P$20_P$4") (pintype "bidirectional"))
    )
    (net (code "90") (name "unconnected-(J1-SBU1-PadB8)") (class "Default")
      (node (ref "J1") (pin "B8") (pinfunction "SBU1_B8") (pintype "bidirectional"))
    )
    (net (code "91") (name "unconnected-(J1-SBU2-PadA8)") (class "Default")
      (node (ref "J1") (pin "A8") (pinfunction "SBU2_A8") (pintype "bidirectional"))
    )
    (net (code "92") (name "unconnected-(K1-Pad3)") (class "Default")
      (node (ref "K1") (pin "3") (pinfunction "3_3") (pintype "bidirectional"))
    )
    (net (code "93") (name "unconnected-(RGB4-1-DOUT-Pad1_DOUT)") (class "Default")
      (node (ref "RGB4") (pin "1_DOUT") (pinfunction "1-DOUT_1_DOUT") (pintype "bidirectional"))
    )
    (net (code "94") (name "unconnected-(U3-*GPIO6,SD_CLK,SPICLK,HS1_CLK,U1CTS-Pad20)") (class "Default")
      (node (ref "U3") (pin "20") (pinfunction "*GPIO6,SD_CLK,SPICLK,HS1_CLK,U1CTS_20") (pintype "bidirectional"))
    )
    (net (code "95") (name "unconnected-(U3-*GPIO7,SD_DATA0,SPIQ,HS1_DATA0,U2RTS-Pad21)") (class "Default")
      (node (ref "U3") (pin "21") (pinfunction "*GPIO7,SD_DATA0,SPIQ,HS1_DATA0,U2RTS_21") (pintype "bidirectional"))
    )
    (net (code "96") (name "unconnected-(U3-*GPIO8,SD_DATA1,SPID,HS1_DATA1,U2CTS-Pad22)") (class "Default")
      (node (ref "U3") (pin "22") (pinfunction "*GPIO8,SD_DATA1,SPID,HS1_DATA1,U2CTS_22") (pintype "bidirectional"))
    )
    (net (code "97") (name "unconnected-(U3-*GPIO9,SD_DATA2,SPIHD,HS1_DATA2,U1RXD-Pad17)") (class "Default")
      (node (ref "U3") (pin "17") (pinfunction "*GPIO9,SD_DATA2,SPIHD,HS1_DATA2,U1RXD_17") (pintype "bidirectional"))
    )
    (net (code "98") (name "unconnected-(U3-*GPIO10,SD_DATA3,SPIWP,HS1_DATA3,U1TXD-Pad18)") (class "Default")
      (node (ref "U3") (pin "18") (pinfunction "*GPIO10,SD_DATA3,SPIWP,HS1_DATA3,U1TXD_18") (pintype "bidirectional"))
    )
    (net (code "99") (name "unconnected-(U3-*GPIO11,SD_CMD,SPICS0,HS1_CMD,U1RTS-Pad19)") (class "Default")
      (node (ref "U3") (pin "19") (pinfunction "*GPIO11,SD_CMD,SPICS0,HS1_CMD,U1RTS_19") (pintype "bidirectional"))
    )
    (net (code "100") (name "unconnected-(U3-NC-Pad27)") (class "Default")
      (node (ref "U3") (pin "27") (pinfunction "NC_27") (pintype "bidirectional"))
    )
    (net (code "101") (name "unconnected-(U3-NC-Pad28)") (class "Default")
      (node (ref "U3") (pin "28") (pinfunction "NC_28") (pintype "bidirectional"))
    )
    (net (code "102") (name "unconnected-(U3-NC-Pad32)") (class "Default")
      (node (ref "U3") (pin "32") (pinfunction "NC_32") (pintype "bidirectional"))
    )
    (net (code "103") (name "unconnected-(U6-CTS#-Pad9)") (class "Default")
      (node (ref "U6") (pin "9") (pinfunction "CTS#_9") (pintype "bidirectional"))
    )
    (net (code "104") (name "unconnected-(U6-DCD#-Pad12)") (class "Default")
      (node (ref "U6") (pin "12") (pinfunction "DCD#_12") (pintype "bidirectional"))
    )
    (net (code "105") (name "unconnected-(U6-DSR#-Pad10)") (class "Default")
      (node (ref "U6") (pin "10") (pinfunction "DSR#_10") (pintype "bidirectional"))
    )
    (net (code "106") (name "unconnected-(U6-RI#-Pad11)") (class "Default")
      (node (ref "U6") (pin "11") (pinfunction "RI#_11") (pintype "bidirectional"))
    )
    (net (code "107") (name "unconnected-(U6-RS232-Pad15)") (class "Default")
      (node (ref "U6") (pin "15") (pinfunction "RS232_15") (pintype "bidirectional"))
    )
  )
)
